# 612_jetracer_328_214.net
KiCad netlist of a schematic drawn in EAGLE
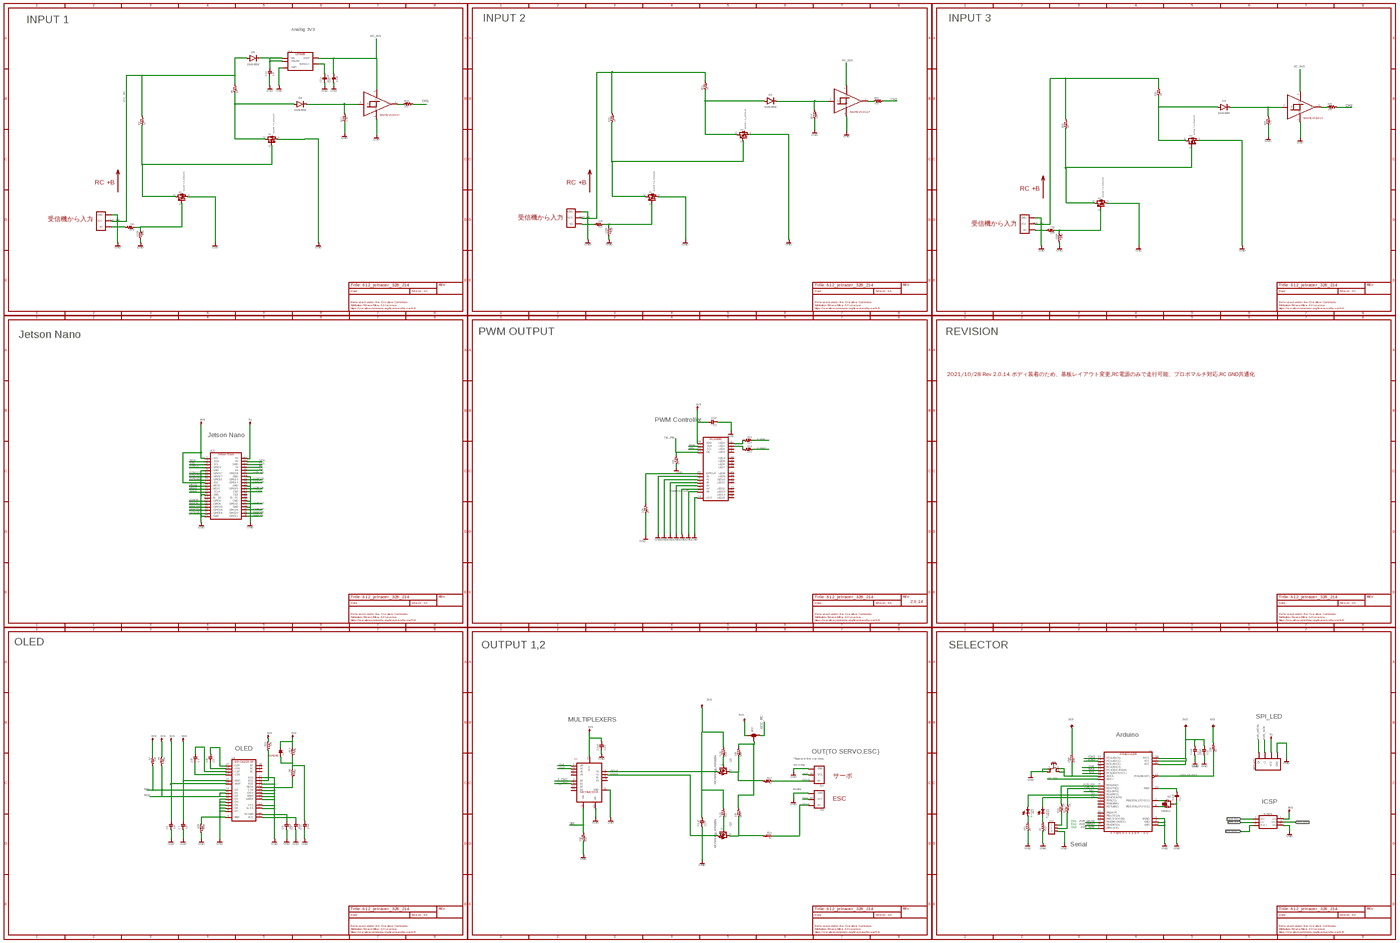
[diagram p0: schematic, sheet 1, overview]
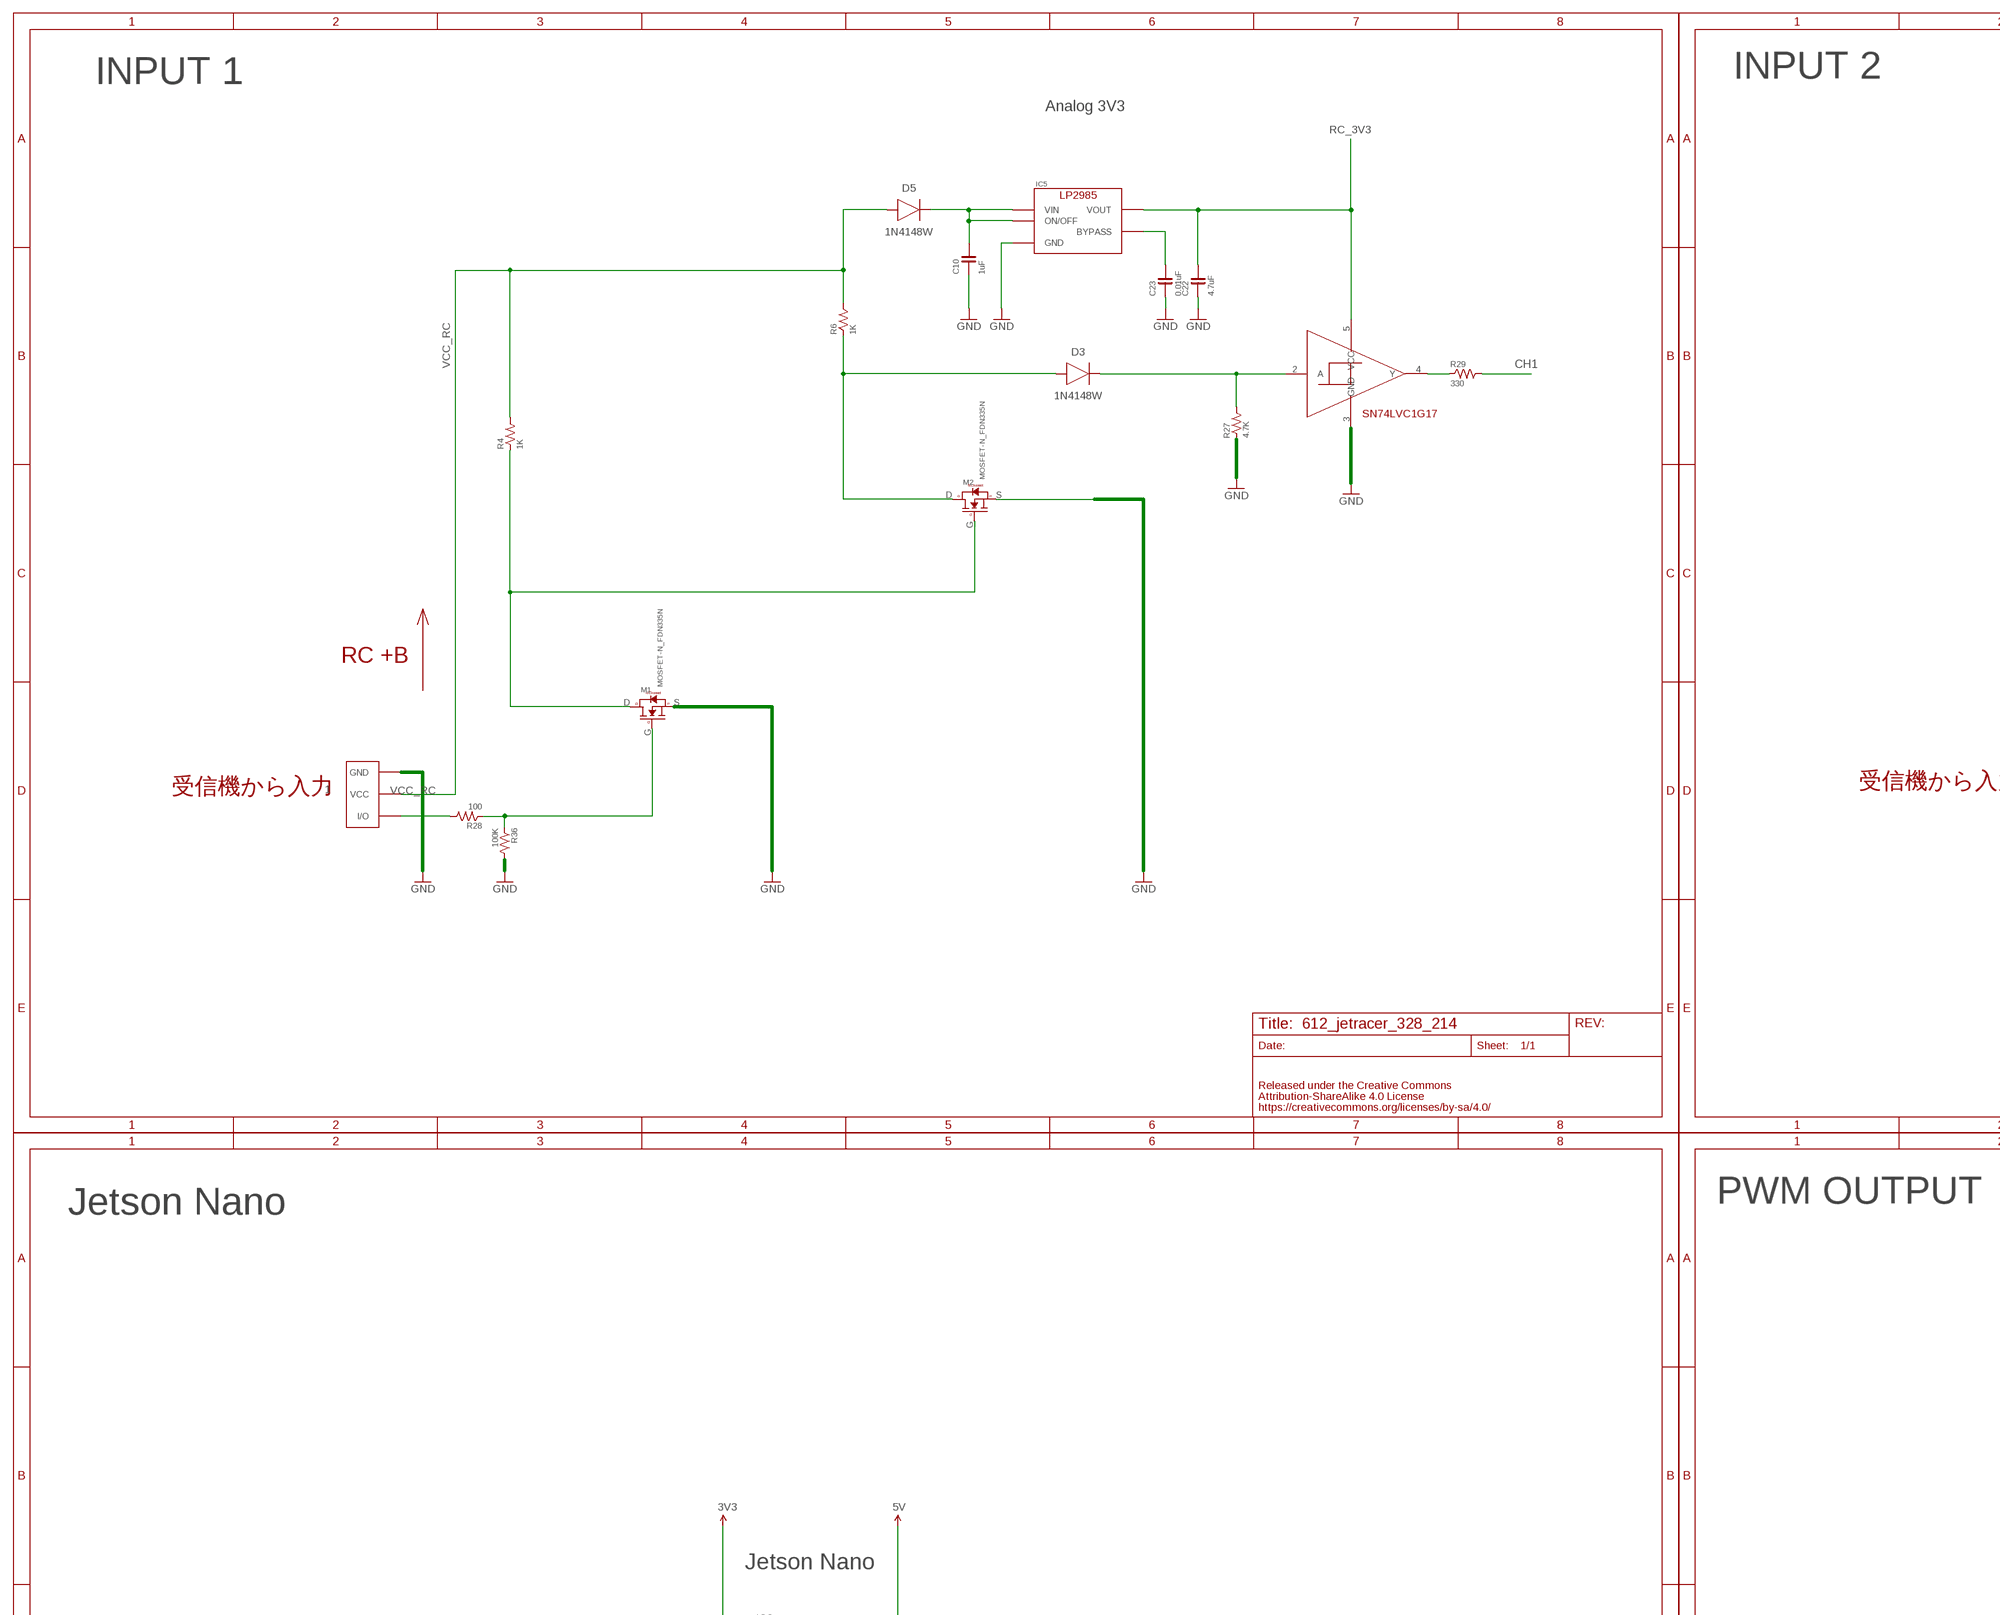
[diagram p1: schematic, sheet 1, part 1 of 6]
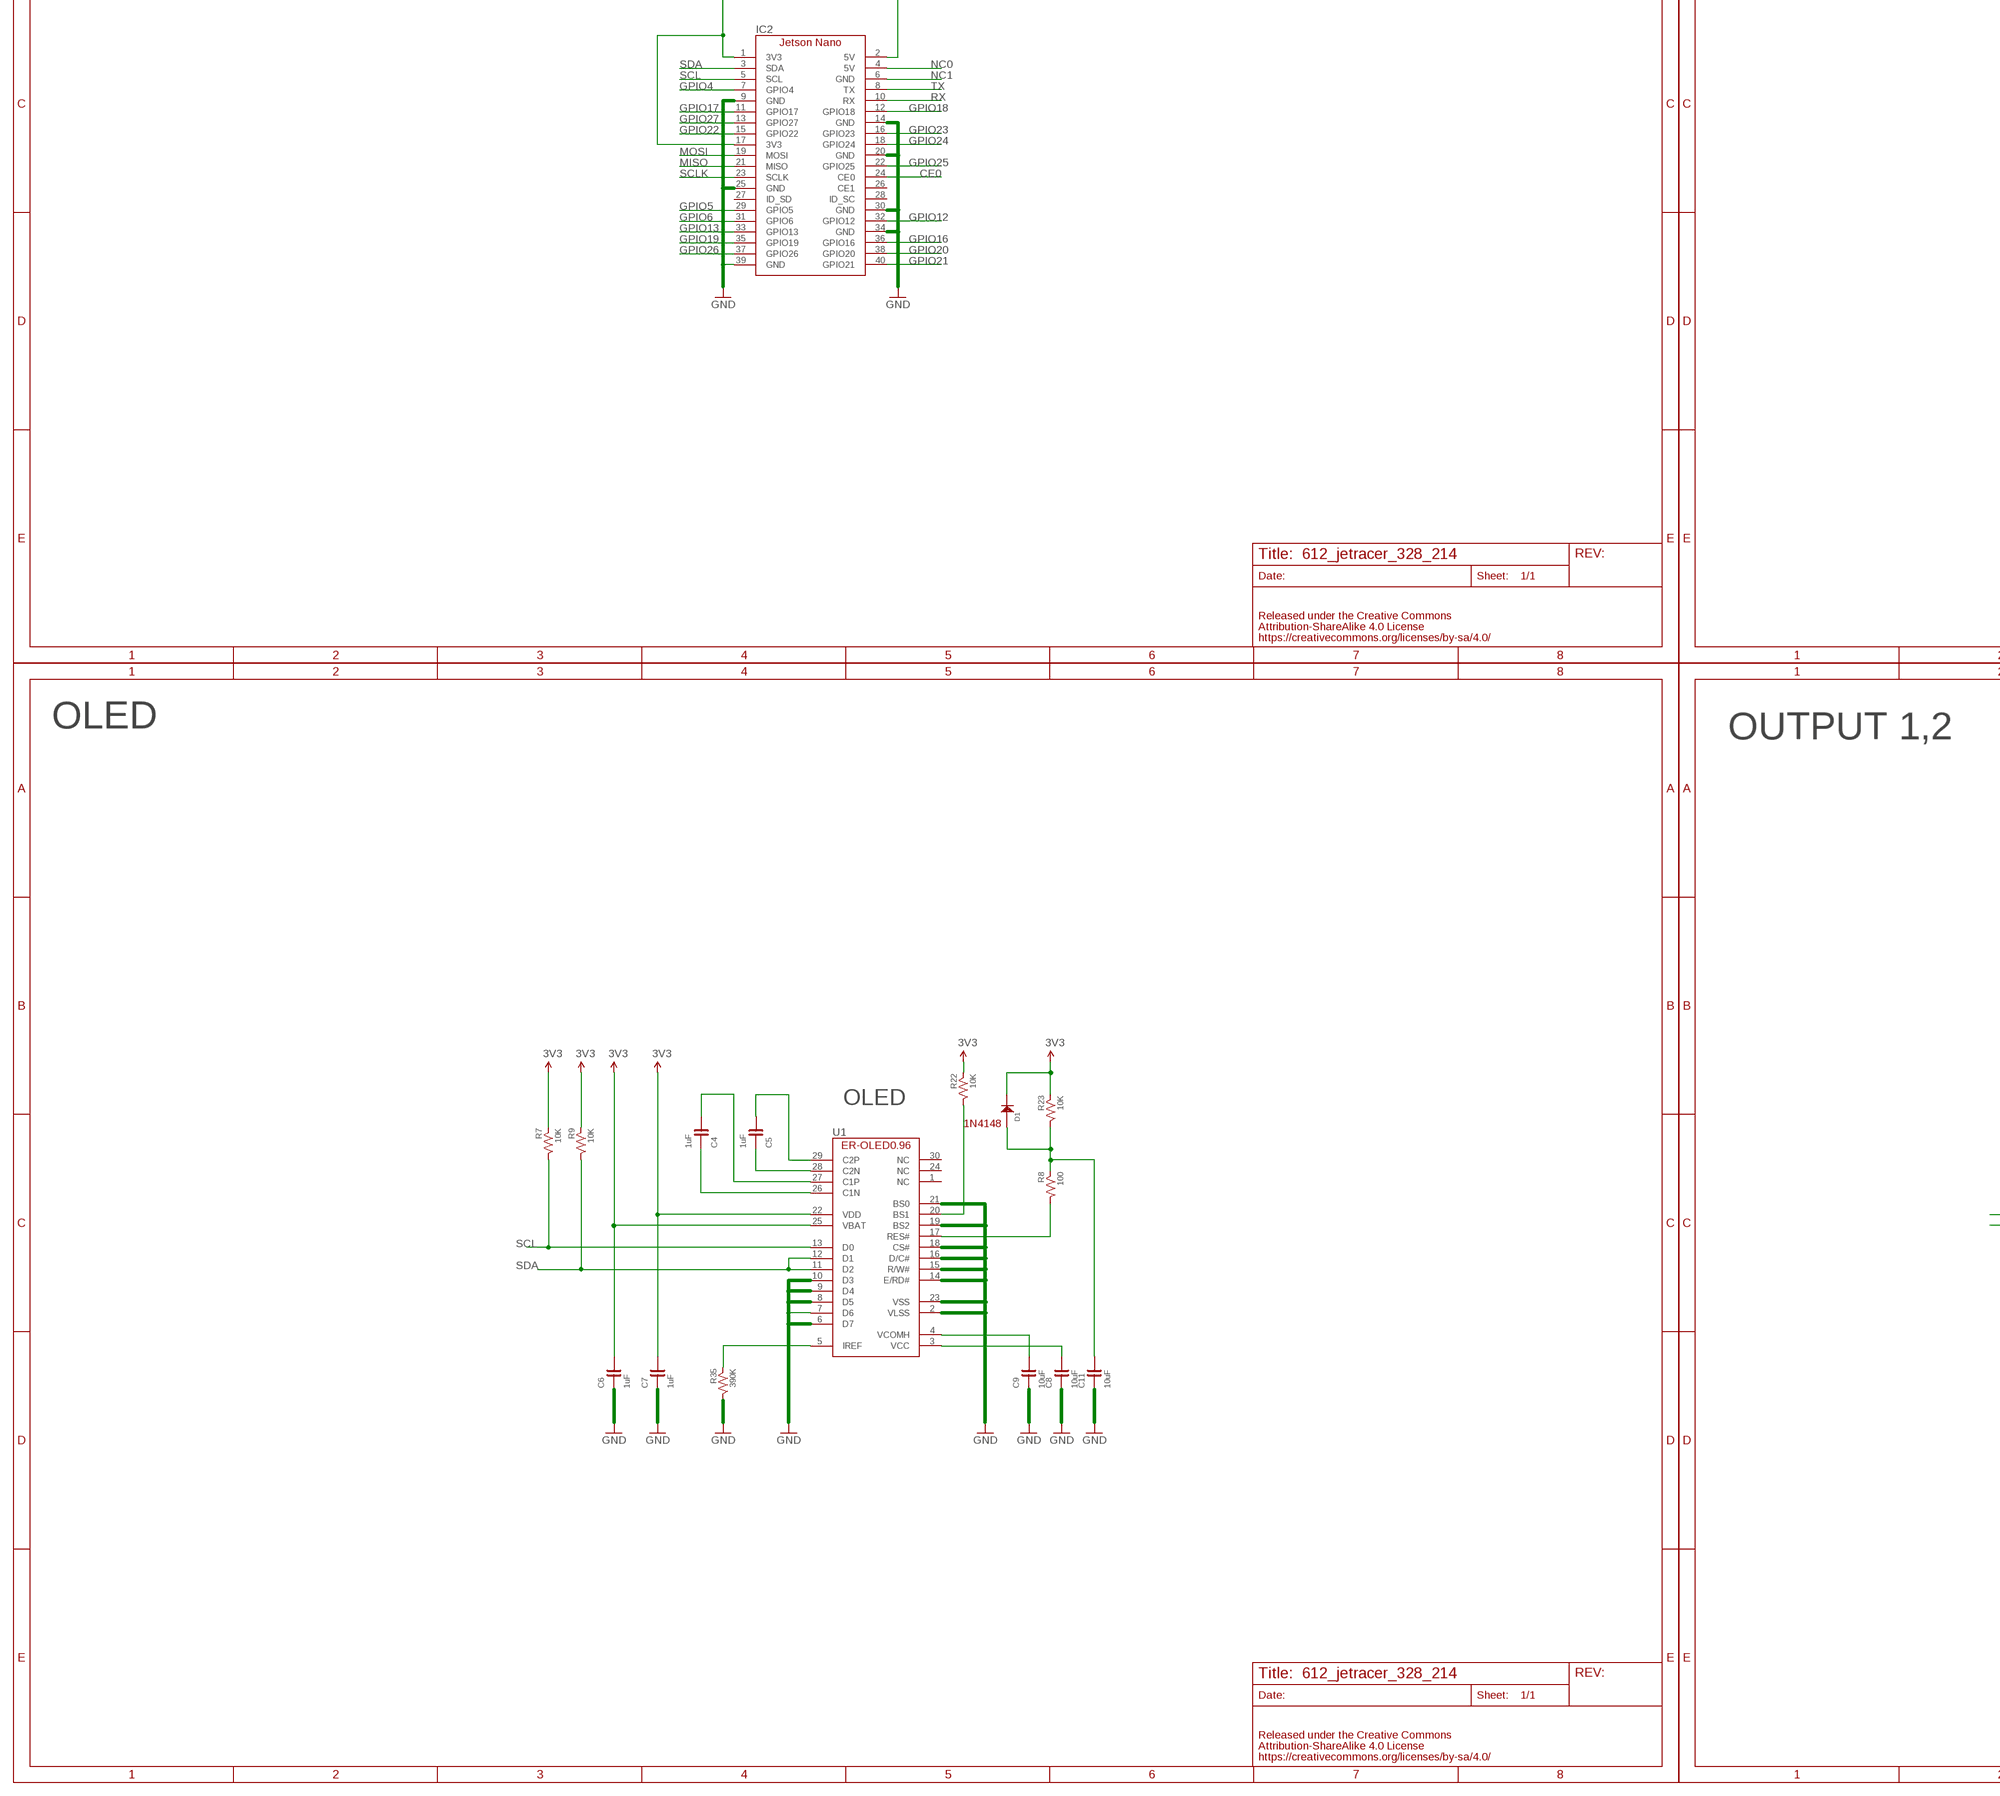
[diagram p2: schematic, sheet 1, part 2 of 6]
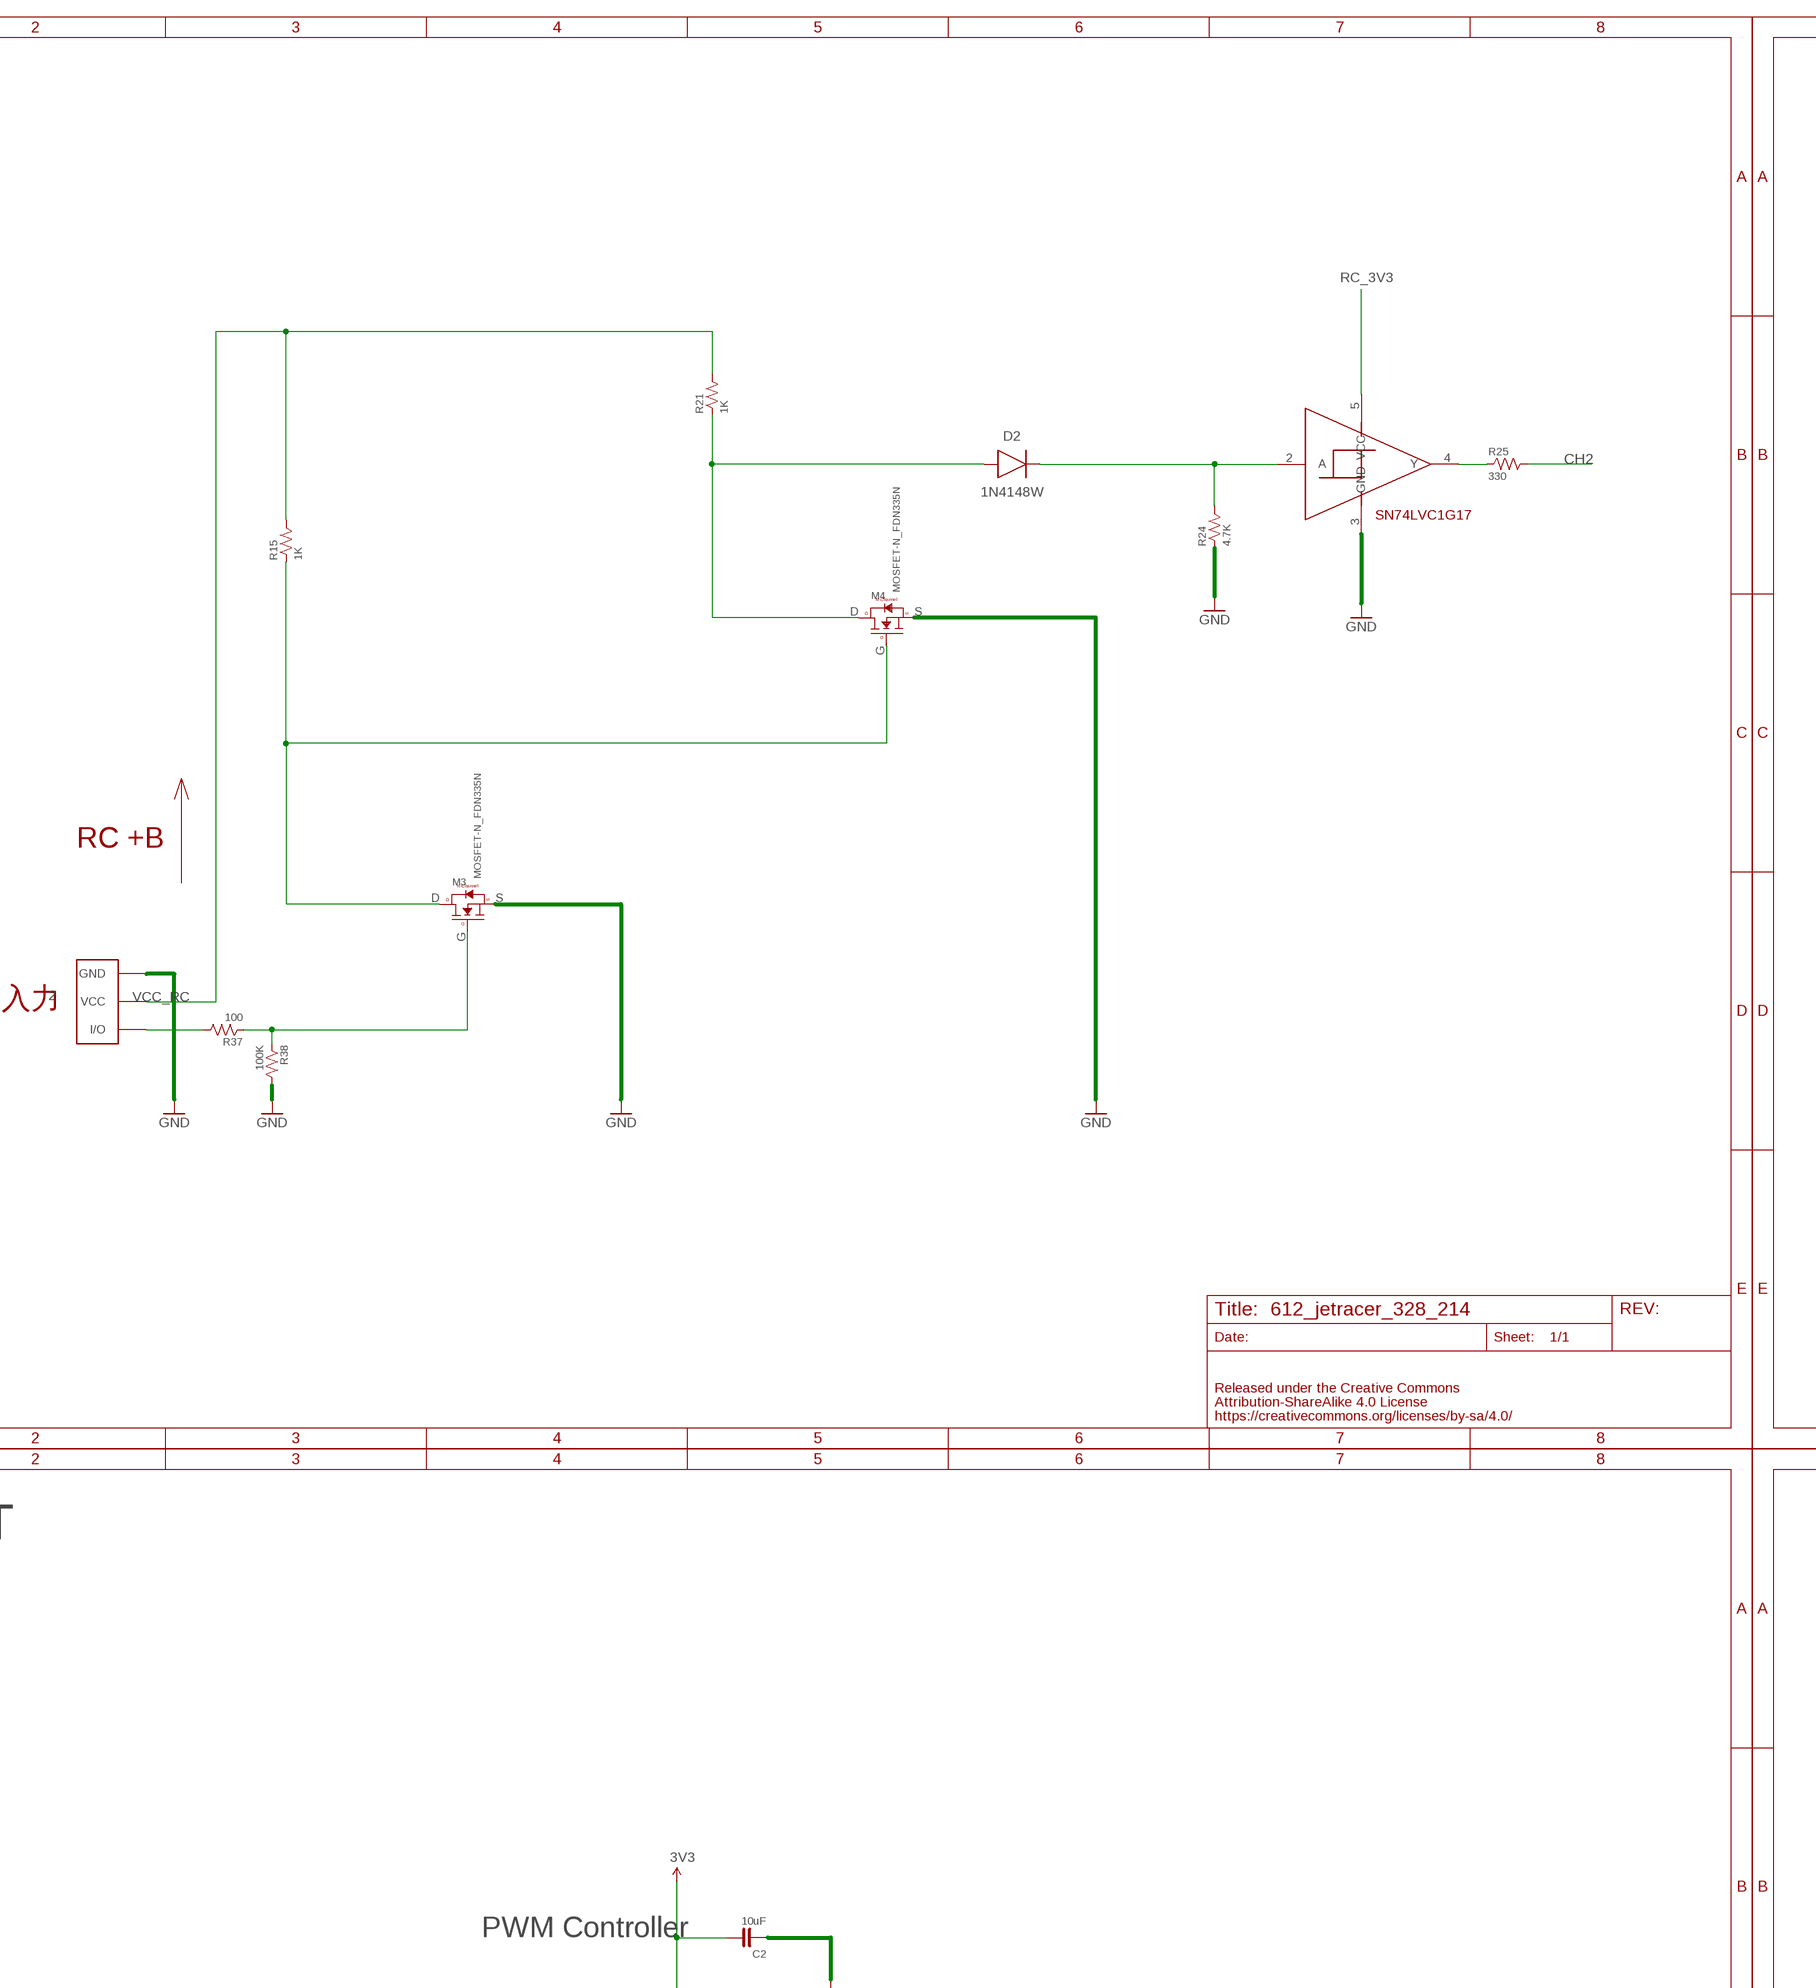
[diagram p3: schematic, sheet 1, part 3 of 6]
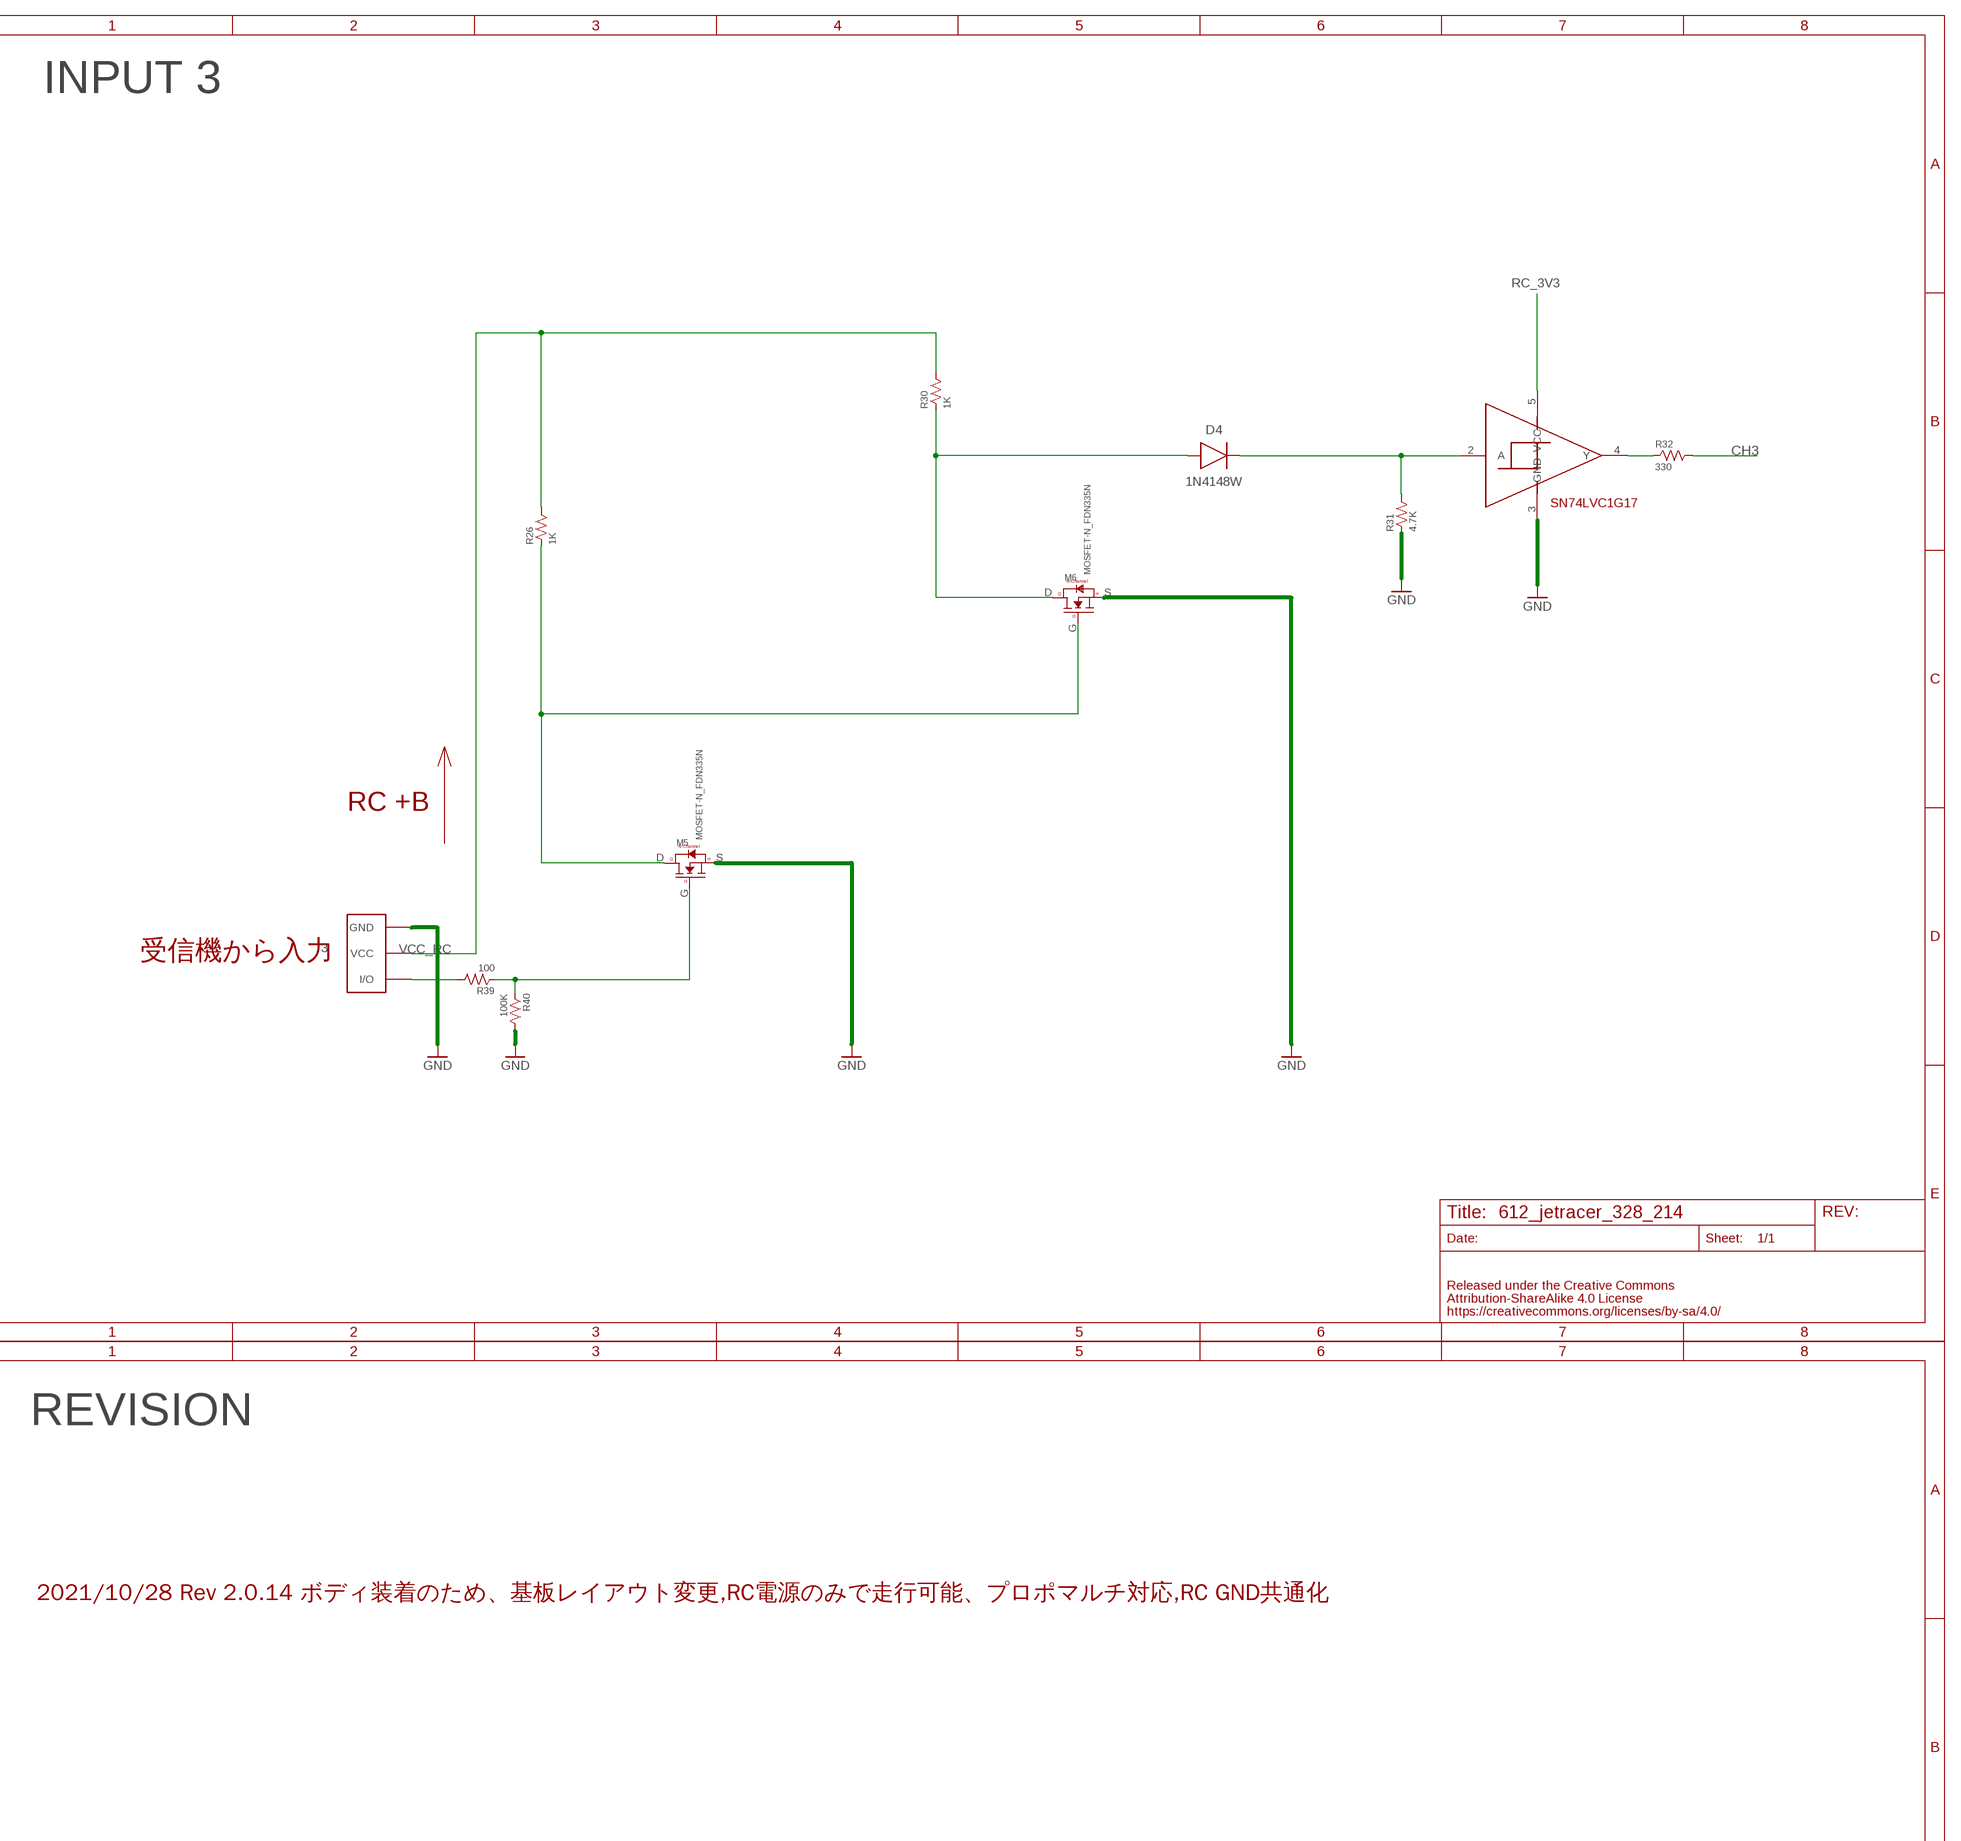
[diagram p4: schematic, sheet 1, part 4 of 6]
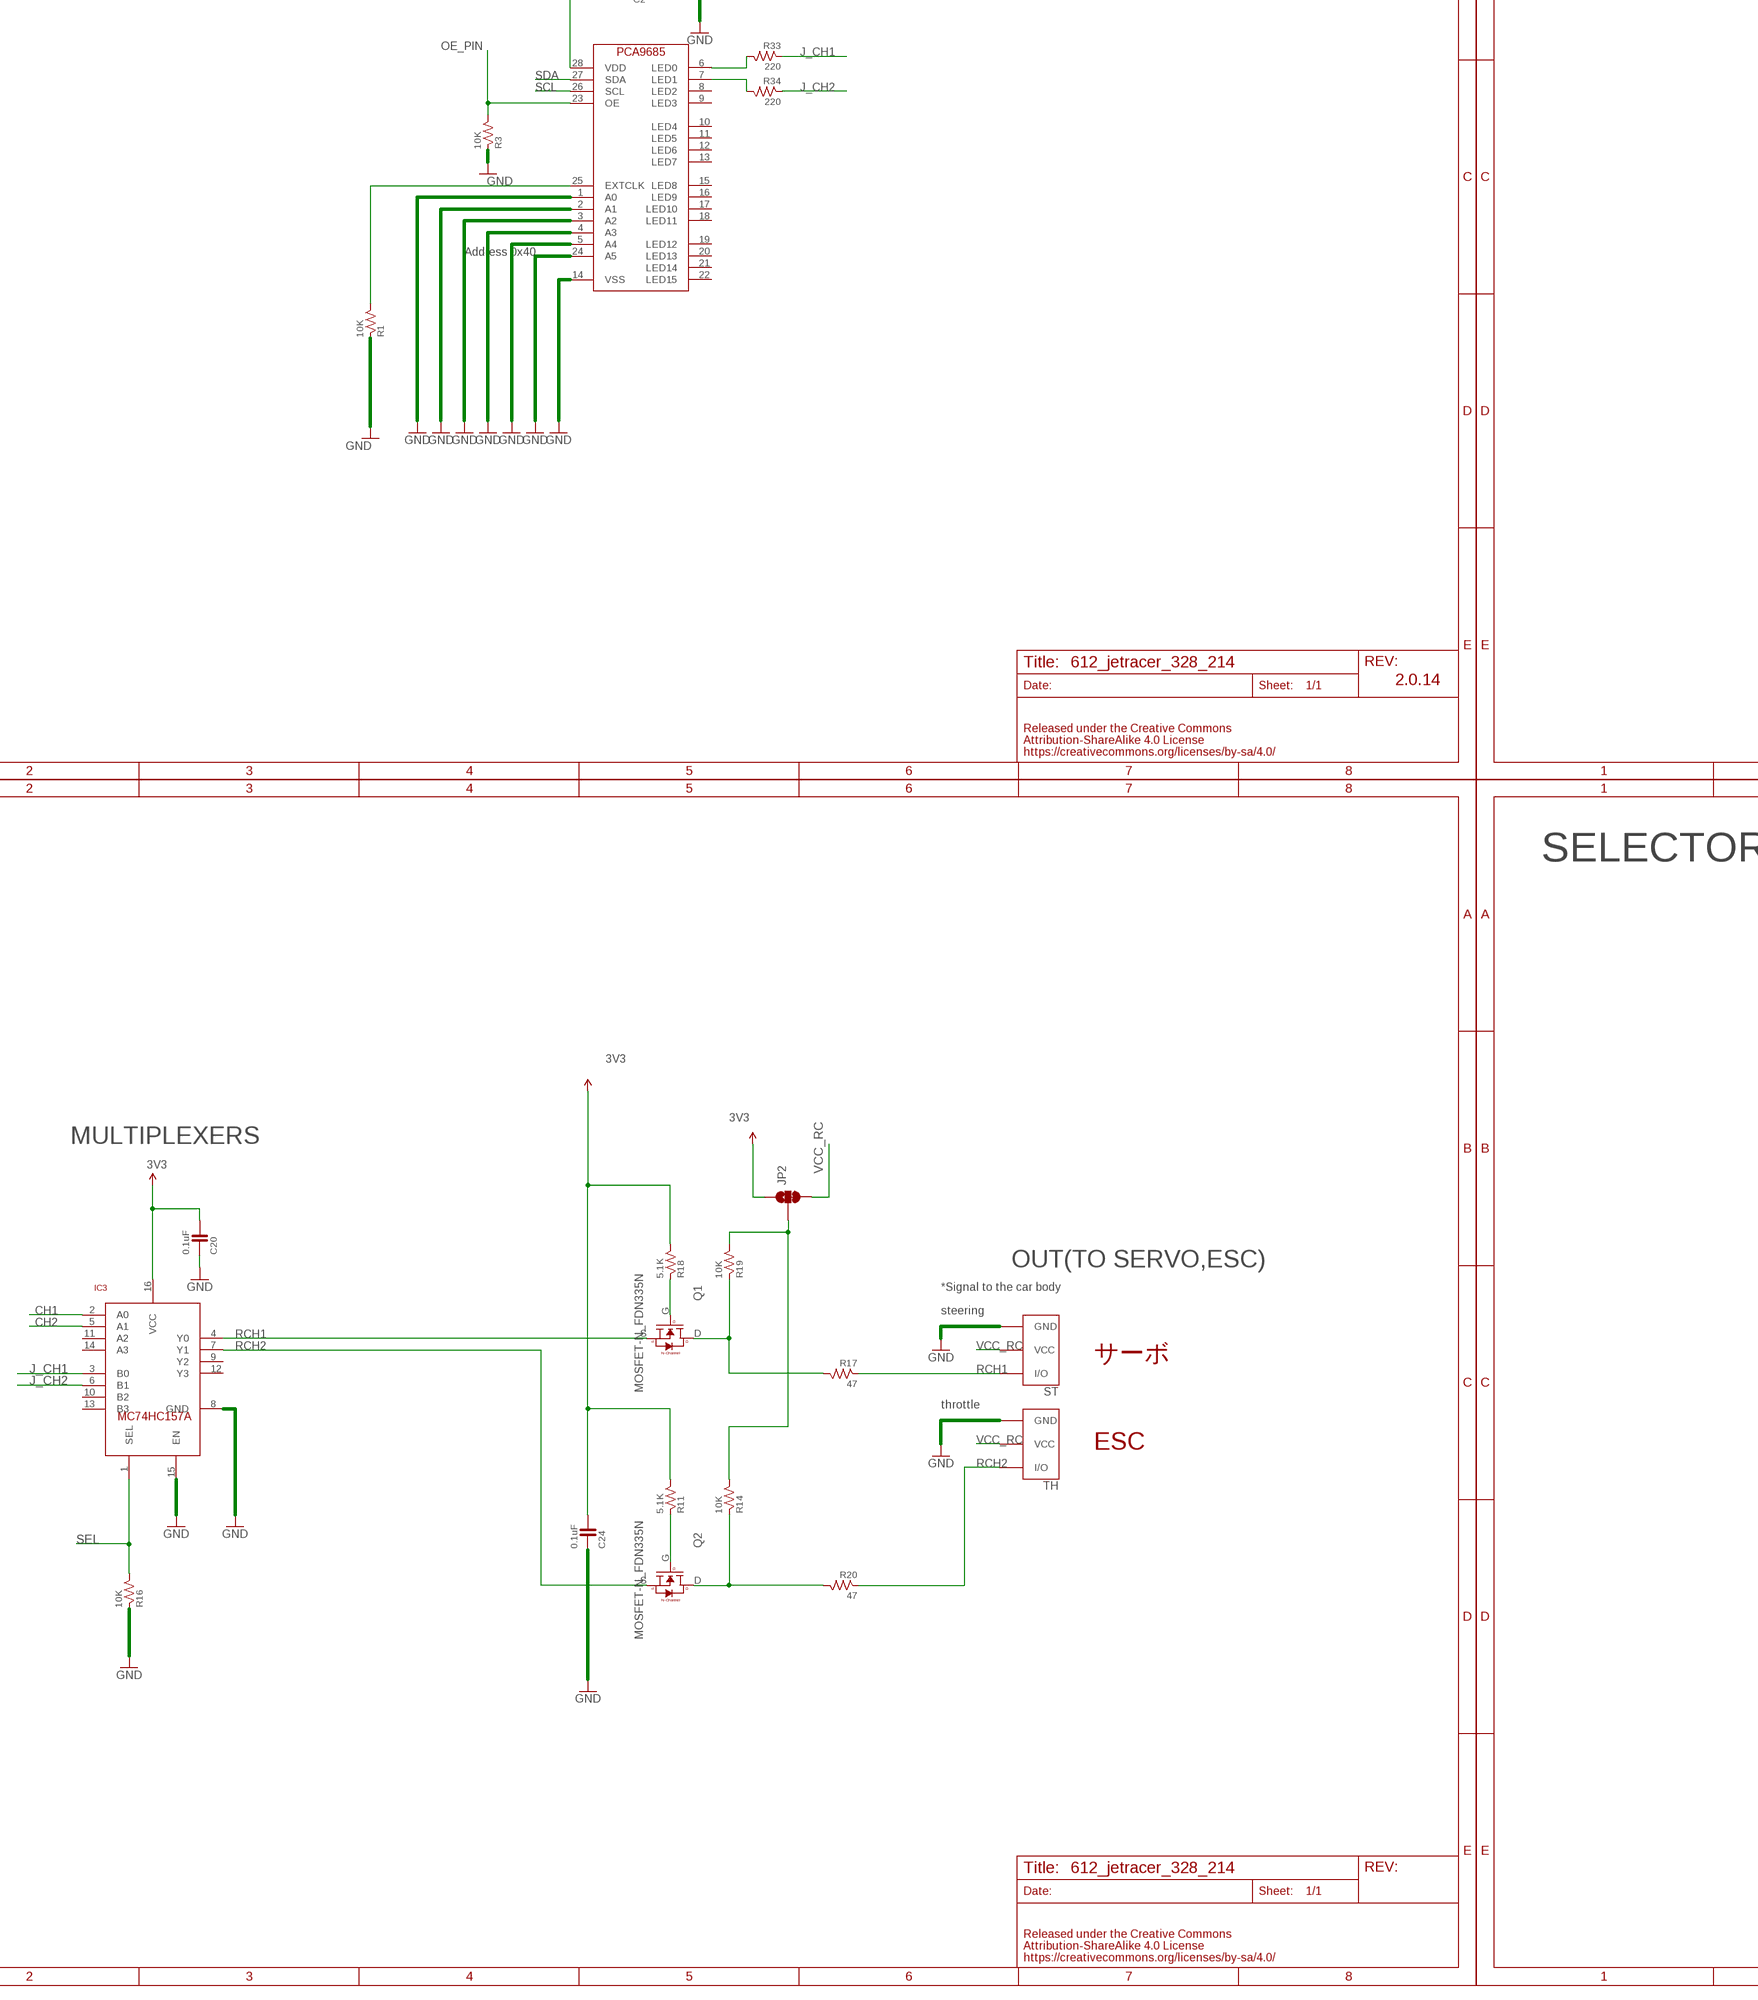
[diagram p5: schematic, sheet 1, part 5 of 6]
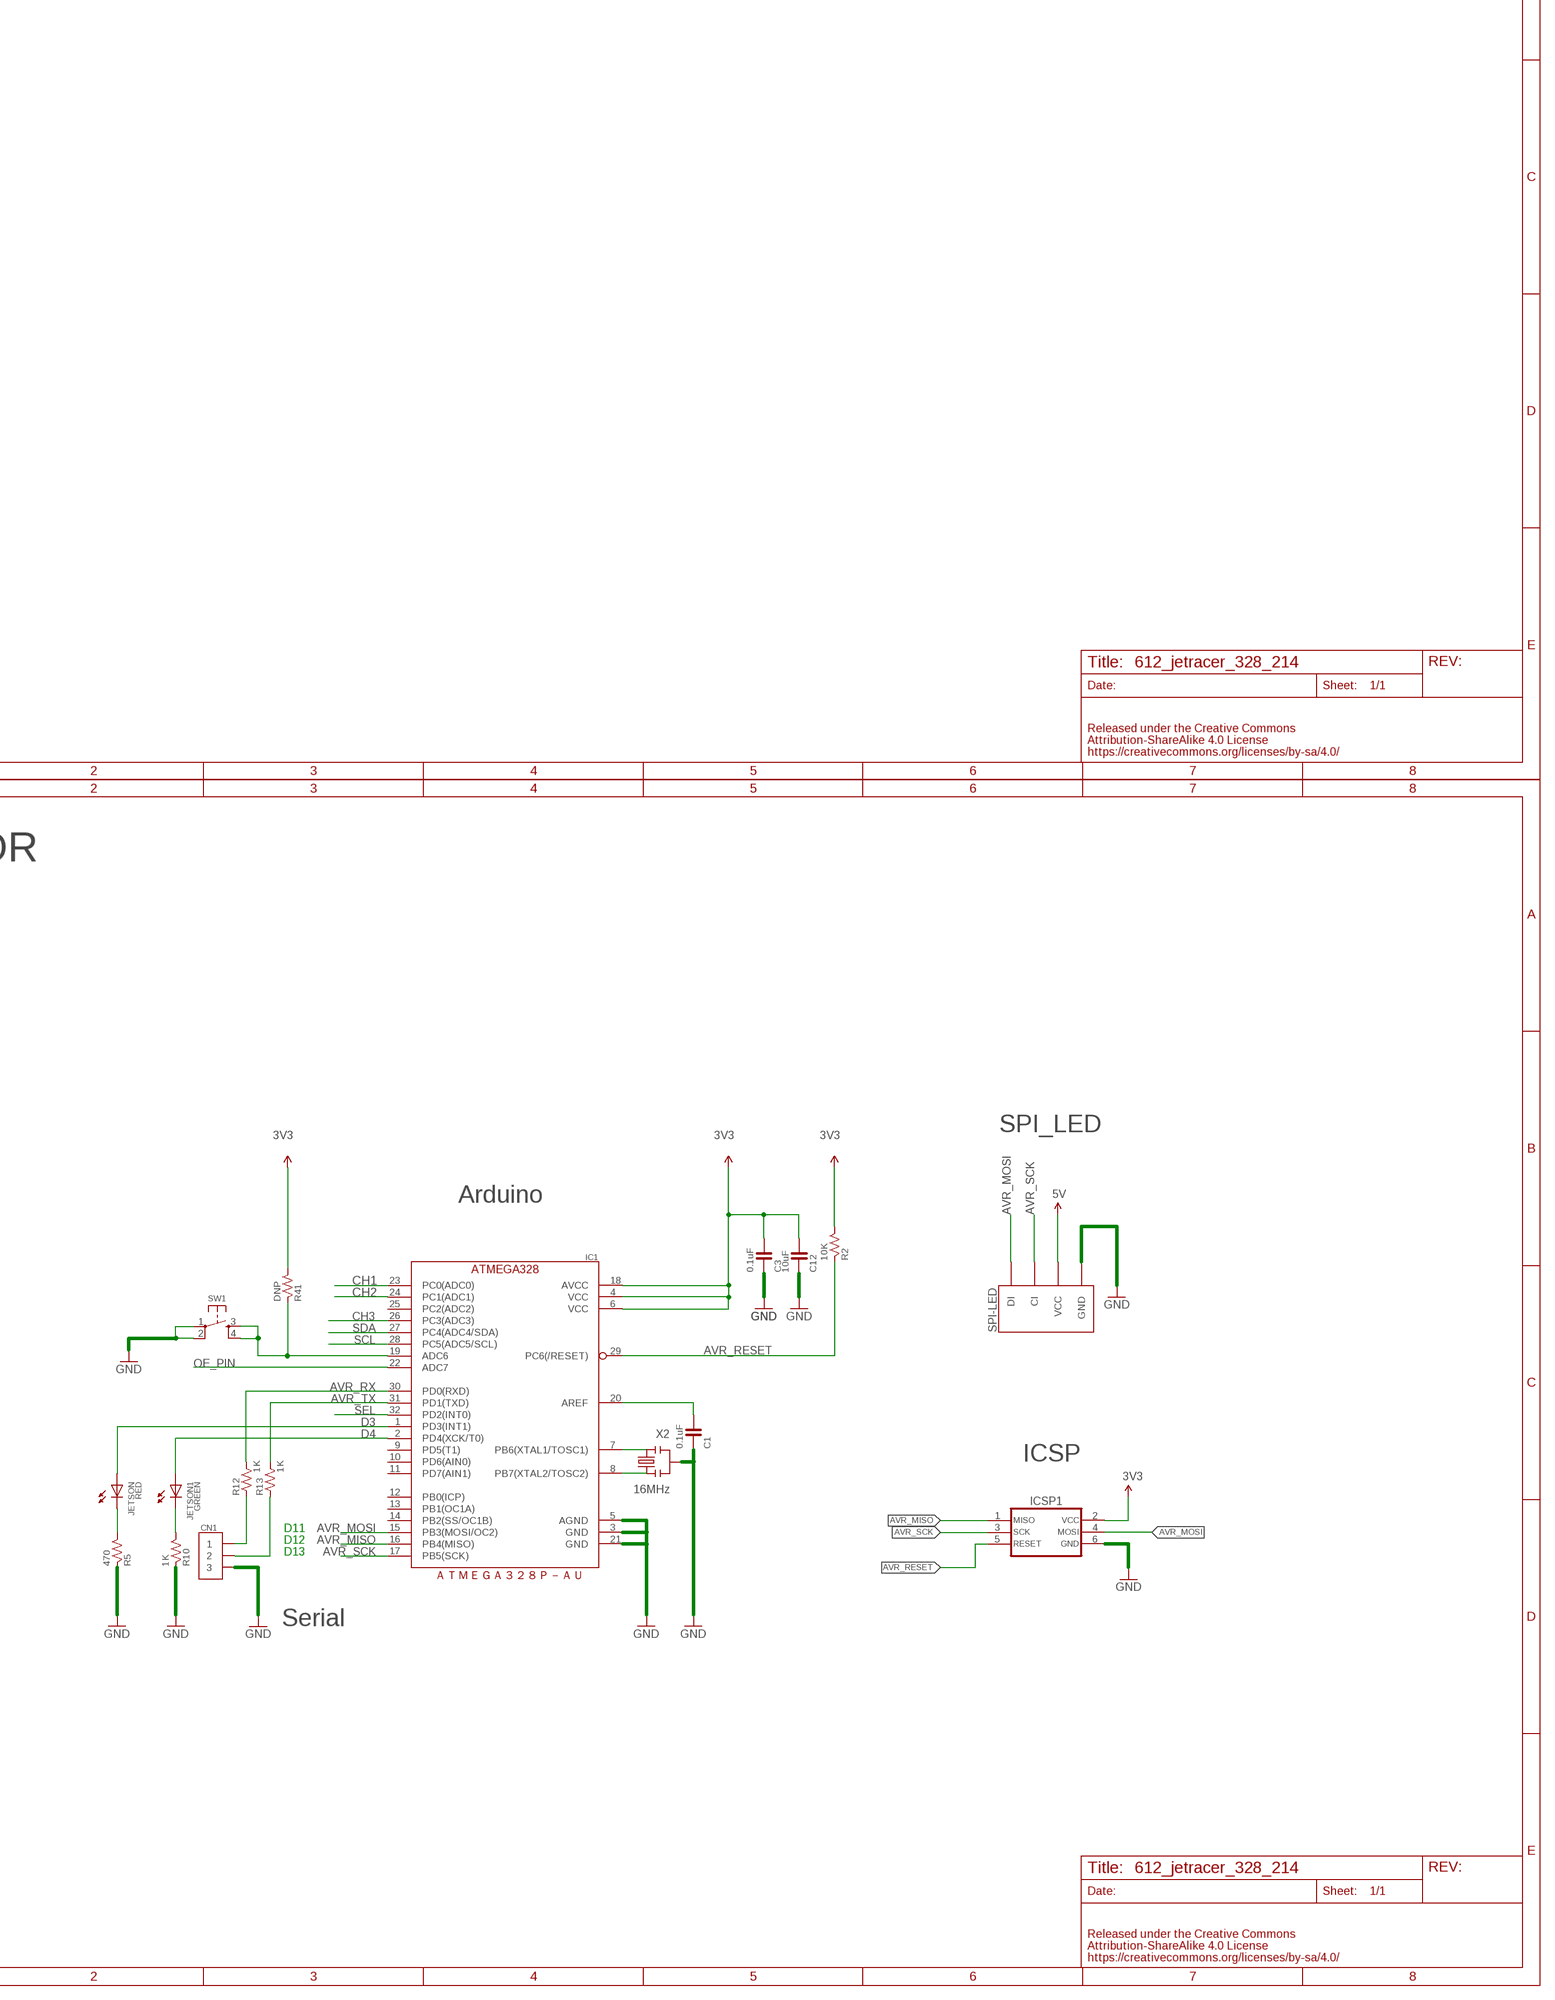
[diagram p6: schematic, sheet 1, part 6 of 6]

(export (version "E")
  (design (tool "Eeschema 10.0.6"))
  (components
    (comp (ref "1")
      (value "FABO_BRICK_3PIN-HEADER")
      (footprint "eagle-import:FABO_BRICK_3PIN_HEADER")
      (libsource (lib "eagle-import") (part "FABO_BRICK_3PIN-HEADER"))
    )
    (comp (ref "2")
      (value "FABO_BRICK_3PIN-HEADER")
      (footprint "eagle-import:FABO_BRICK_3PIN_HEADER")
      (libsource (lib "eagle-import") (part "FABO_BRICK_3PIN-HEADER"))
    )
    (comp (ref "3")
      (value "FABO_BRICK_3PIN-HEADER")
      (footprint "eagle-import:FABO_BRICK_3PIN_HEADER")
      (libsource (lib "eagle-import") (part "FABO_BRICK_3PIN-HEADER"))
    )
    (comp (ref "C1")
      (value "0.1uF")
      (footprint "eagle-import:0603")
      (libsource (lib "eagle-import") (part "CAPACITOR-0603"))
    )
    (comp (ref "C2")
      (value "10uF")
      (footprint "eagle-import:0603")
      (libsource (lib "eagle-import") (part "CAPACITOR-0603"))
    )
    (comp (ref "C3")
      (value "0.1uF")
      (footprint "eagle-import:0603")
      (libsource (lib "eagle-import") (part "CAPACITOR-0603"))
    )
    (comp (ref "C4")
      (value "1uF")
      (footprint "eagle-import:0603")
      (libsource (lib "eagle-import") (part "CAPACITOR-0603"))
    )
    (comp (ref "C5")
      (value "1uF")
      (footprint "eagle-import:0603")
      (libsource (lib "eagle-import") (part "CAPACITOR-0603"))
    )
    (comp (ref "C6")
      (value "1uF")
      (footprint "eagle-import:0603")
      (libsource (lib "eagle-import") (part "CAPACITOR-0603"))
    )
    (comp (ref "C7")
      (value "1uF")
      (footprint "eagle-import:0603")
      (libsource (lib "eagle-import") (part "CAPACITOR-0603"))
    )
    (comp (ref "C8")
      (value "10uF")
      (footprint "eagle-import:0603")
      (libsource (lib "eagle-import") (part "CAPACITOR-0603"))
    )
    (comp (ref "C9")
      (value "10uF")
      (footprint "eagle-import:0603")
      (libsource (lib "eagle-import") (part "CAPACITOR-0603"))
    )
    (comp (ref "C10")
      (value "1uF")
      (footprint "eagle-import:0603")
      (libsource (lib "eagle-import") (part "CAPACITOR-0603"))
    )
    (comp (ref "C11")
      (value "10uF")
      (footprint "eagle-import:0603")
      (libsource (lib "eagle-import") (part "CAPACITOR-0603"))
    )
    (comp (ref "C12")
      (value "10uF")
      (footprint "eagle-import:0603")
      (libsource (lib "eagle-import") (part "CAPACITOR-0603"))
    )
    (comp (ref "C20")
      (value "0.1uF")
      (footprint "eagle-import:0603")
      (libsource (lib "eagle-import") (part "CAPACITOR-0603"))
    )
    (comp (ref "C22")
      (value "4.7uF")
      (footprint "eagle-import:0603")
      (libsource (lib "eagle-import") (part "CAPACITOR-0603"))
    )
    (comp (ref "C23")
      (value "0.01uF")
      (footprint "eagle-import:0603")
      (libsource (lib "eagle-import") (part "CAPACITOR-0603"))
    )
    (comp (ref "C24")
      (value "0.1uF")
      (footprint "eagle-import:0603")
      (fields (field (name "SPICEPREFIX") "C"))
      (libsource (lib "eagle-import") (part "CAPACITOR-0603"))
    )
    (comp (ref "CN1")
      (value "PIN_1X3")
      (footprint "eagle-import:PIN_1X3")
      (libsource (lib "eagle-import") (part "PIN_1X3"))
    )
    (comp (ref "D1")
      (value "1N4148")
      (footprint "eagle-import:1N4148W")
      (libsource (lib "eagle-import") (part "1N4148"))
    )
    (comp (ref "D2")
      (value "1N4148W")
      (footprint "eagle-import:SOD3715X135")
      (fields (field (name "MANUFACTURER") "Diodes Incorporated"))
      (libsource (lib "eagle-import") (part "DIODE__SOD123G1N4148W-7-F"))
    )
    (comp (ref "D3")
      (value "1N4148W")
      (footprint "eagle-import:SOD3715X135")
      (fields (field (name "MANUFACTURER") "Diodes Incorporated"))
      (libsource (lib "eagle-import") (part "DIODE__SOD123G1N4148W-7-F"))
    )
    (comp (ref "D4")
      (value "1N4148W")
      (footprint "eagle-import:SOD3715X135")
      (fields (field (name "MANUFACTURER") "Diodes Incorporated"))
      (libsource (lib "eagle-import") (part "DIODE__SOD123G1N4148W-7-F"))
    )
    (comp (ref "D5")
      (value "1N4148W")
      (footprint "eagle-import:SOD3715X135")
      (fields (field (name "MANUFACTURER") "Diodes Incorporated"))
      (libsource (lib "eagle-import") (part "DIODE__SOD123G1N4148W-7-F"))
    )
    (comp (ref "IC1")
      (value "ATMEGA328P-AU")
      (footprint "eagle-import:TQFP-32")
      (libsource (lib "eagle-import") (part "ATMEGA328P-AU"))
    )
    (comp (ref "IC2")
      (value "JETSON_NANO_NOBORDER")
      (footprint "eagle-import:JETSON_NANO_NOBOARDER")
      (libsource (lib "eagle-import") (part "JETSON_NANO_NOBORDER"))
    )
    (comp (ref "IC3")
      (value "MULTIPLEXERSMC74HC157A")
      (footprint "eagle-import:TSSOP-16")
      (libsource (lib "eagle-import") (part "MULTIPLEXERSMC74HC157A"))
    )
    (comp (ref "IC4")
      (value "PCA9685")
      (footprint "eagle-import:PCA9685")
      (libsource (lib "eagle-import") (part "PCA9685"))
    )
    (comp (ref "IC5")
      (value "LP2985-33DBV")
      (footprint "eagle-import:SOT-23-5")
      (libsource (lib "eagle-import") (part "LP2985-33DBV"))
    )
    (comp (ref "ICSP1")
      (value "ICSP_AVR-TC_NOHOLE")
      (footprint "eagle-import:TC2030")
      (libsource (lib "eagle-import") (part "ICSP_AVR-TC_NOHOLE"))
    )
    (comp (ref "JETSON")
      (value "GREEN")
      (footprint "eagle-import:0603")
      (libsource (lib "eagle-import") (part "LED-0603"))
    )
    (comp (ref "JETSON1")
      (value "RED")
      (footprint "eagle-import:0603")
      (libsource (lib "eagle-import") (part "LED-0603"))
    )
    (comp (ref "JP2")
      (value "JUMPER-SMT_3_1-NC_TRACE_SILK")
      (footprint "eagle-import:SMT-JUMPER_3_1-NC_TRACE_SILK")
      (libsource (lib "eagle-import") (part "JUMPER-SMT_3_1-NC_TRACE_SILK"))
    )
    (comp (ref "M1")
      (value "MOSFET-N_FDN335N")
      (footprint "eagle-import:SUPERSOT-3")
      (libsource (lib "eagle-import") (part "MOSFET-N_FDN335N"))
    )
    (comp (ref "M2")
      (value "MOSFET-N_FDN335N")
      (footprint "eagle-import:SUPERSOT-3")
      (libsource (lib "eagle-import") (part "MOSFET-N_FDN335N"))
    )
    (comp (ref "M3")
      (value "MOSFET-N_FDN335N")
      (footprint "eagle-import:SUPERSOT-3")
      (libsource (lib "eagle-import") (part "MOSFET-N_FDN335N"))
    )
    (comp (ref "M4")
      (value "MOSFET-N_FDN335N")
      (footprint "eagle-import:SUPERSOT-3")
      (libsource (lib "eagle-import") (part "MOSFET-N_FDN335N"))
    )
    (comp (ref "M5")
      (value "MOSFET-N_FDN335N")
      (footprint "eagle-import:SUPERSOT-3")
      (libsource (lib "eagle-import") (part "MOSFET-N_FDN335N"))
    )
    (comp (ref "M6")
      (value "MOSFET-N_FDN335N")
      (footprint "eagle-import:SUPERSOT-3")
      (libsource (lib "eagle-import") (part "MOSFET-N_FDN335N"))
    )
    (comp (ref "Q1")
      (value "MOSFET-N_FDN335N")
      (footprint "eagle-import:SUPERSOT-3")
      (libsource (lib "eagle-import") (part "MOSFET-N_FDN335N"))
    )
    (comp (ref "Q2")
      (value "MOSFET-N_FDN335N")
      (footprint "eagle-import:SUPERSOT-3")
      (libsource (lib "eagle-import") (part "MOSFET-N_FDN335N"))
    )
    (comp (ref "R1")
      (value "10K")
      (footprint "eagle-import:0603")
      (libsource (lib "eagle-import") (part "RESISTOR-0603"))
    )
    (comp (ref "R2")
      (value "10K")
      (footprint "eagle-import:0603")
      (libsource (lib "eagle-import") (part "RESISTOR-0603"))
    )
    (comp (ref "R3")
      (value "10K")
      (footprint "eagle-import:0603")
      (libsource (lib "eagle-import") (part "RESISTOR-0603"))
    )
    (comp (ref "R4")
      (value "1K")
      (footprint "eagle-import:0603")
      (libsource (lib "eagle-import") (part "RESISTOR-0603"))
    )
    (comp (ref "R5")
      (value "470")
      (footprint "eagle-import:0603")
      (libsource (lib "eagle-import") (part "RESISTOR-0603"))
    )
    (comp (ref "R6")
      (value "1K")
      (footprint "eagle-import:0603")
      (libsource (lib "eagle-import") (part "RESISTOR-0603"))
    )
    (comp (ref "R7")
      (value "10K")
      (footprint "eagle-import:0603")
      (libsource (lib "eagle-import") (part "RESISTOR-0603"))
    )
    (comp (ref "R8")
      (value "100")
      (footprint "eagle-import:0603")
      (libsource (lib "eagle-import") (part "RESISTOR-0603"))
    )
    (comp (ref "R9")
      (value "10K")
      (footprint "eagle-import:0603")
      (libsource (lib "eagle-import") (part "RESISTOR-0603"))
    )
    (comp (ref "R10")
      (value "1K")
      (footprint "eagle-import:0603")
      (libsource (lib "eagle-import") (part "RESISTOR-0603"))
    )
    (comp (ref "R11")
      (value "5.1K")
      (footprint "eagle-import:0603")
      (libsource (lib "eagle-import") (part "RESISTOR-0603"))
    )
    (comp (ref "R12")
      (value "1K")
      (footprint "eagle-import:0603")
      (libsource (lib "eagle-import") (part "RESISTOR-0603"))
    )
    (comp (ref "R13")
      (value "1K")
      (footprint "eagle-import:0603")
      (libsource (lib "eagle-import") (part "RESISTOR-0603"))
    )
    (comp (ref "R14")
      (value "10K")
      (footprint "eagle-import:0603")
      (libsource (lib "eagle-import") (part "RESISTOR-0603"))
    )
    (comp (ref "R15")
      (value "1K")
      (footprint "eagle-import:0603")
      (libsource (lib "eagle-import") (part "RESISTOR-0603"))
    )
    (comp (ref "R16")
      (value "10K")
      (footprint "eagle-import:0603")
      (libsource (lib "eagle-import") (part "RESISTOR-0603"))
    )
    (comp (ref "R17")
      (value "47")
      (footprint "eagle-import:0603")
      (libsource (lib "eagle-import") (part "RESISTOR-0603"))
    )
    (comp (ref "R18")
      (value "5.1K")
      (footprint "eagle-import:0603")
      (libsource (lib "eagle-import") (part "RESISTOR-0603"))
    )
    (comp (ref "R19")
      (value "10K")
      (footprint "eagle-import:0603")
      (libsource (lib "eagle-import") (part "RESISTOR-0603"))
    )
    (comp (ref "R20")
      (value "47")
      (footprint "eagle-import:0603")
      (libsource (lib "eagle-import") (part "RESISTOR-0603"))
    )
    (comp (ref "R21")
      (value "1K")
      (footprint "eagle-import:0603")
      (libsource (lib "eagle-import") (part "RESISTOR-0603"))
    )
    (comp (ref "R22")
      (value "10K")
      (footprint "eagle-import:0603")
      (libsource (lib "eagle-import") (part "RESISTOR-0603"))
    )
    (comp (ref "R23")
      (value "10K")
      (footprint "eagle-import:0603")
      (libsource (lib "eagle-import") (part "RESISTOR-0603"))
    )
    (comp (ref "R24")
      (value "4.7K")
      (footprint "eagle-import:0603")
      (libsource (lib "eagle-import") (part "RESISTOR-0603"))
    )
    (comp (ref "R25")
      (value "330")
      (footprint "eagle-import:0603")
      (libsource (lib "eagle-import") (part "RESISTOR-0603"))
    )
    (comp (ref "R26")
      (value "1K")
      (footprint "eagle-import:0603")
      (libsource (lib "eagle-import") (part "RESISTOR-0603"))
    )
    (comp (ref "R27")
      (value "4.7K")
      (footprint "eagle-import:0603")
      (libsource (lib "eagle-import") (part "RESISTOR-0603"))
    )
    (comp (ref "R28")
      (value "100")
      (footprint "eagle-import:0603")
      (libsource (lib "eagle-import") (part "RESISTOR-0603"))
    )
    (comp (ref "R29")
      (value "330")
      (footprint "eagle-import:0603")
      (libsource (lib "eagle-import") (part "RESISTOR-0603"))
    )
    (comp (ref "R30")
      (value "1K")
      (footprint "eagle-import:0603")
      (libsource (lib "eagle-import") (part "RESISTOR-0603"))
    )
    (comp (ref "R31")
      (value "4.7K")
      (footprint "eagle-import:0603")
      (libsource (lib "eagle-import") (part "RESISTOR-0603"))
    )
    (comp (ref "R32")
      (value "330")
      (footprint "eagle-import:0603")
      (libsource (lib "eagle-import") (part "RESISTOR-0603"))
    )
    (comp (ref "R33")
      (value "220")
      (footprint "eagle-import:0603")
      (libsource (lib "eagle-import") (part "RESISTOR-0603"))
    )
    (comp (ref "R34")
      (value "220")
      (footprint "eagle-import:0603")
      (libsource (lib "eagle-import") (part "RESISTOR-0603"))
    )
    (comp (ref "R35")
      (value "390K")
      (footprint "eagle-import:0603")
      (libsource (lib "eagle-import") (part "RESISTOR-0603"))
    )
    (comp (ref "R36")
      (value "100K")
      (footprint "eagle-import:0603")
      (libsource (lib "eagle-import") (part "RESISTOR-0603"))
    )
    (comp (ref "R37")
      (value "100")
      (footprint "eagle-import:0603")
      (libsource (lib "eagle-import") (part "RESISTOR-0603"))
    )
    (comp (ref "R38")
      (value "100K")
      (footprint "eagle-import:0603")
      (libsource (lib "eagle-import") (part "RESISTOR-0603"))
    )
    (comp (ref "R39")
      (value "100")
      (footprint "eagle-import:0603")
      (libsource (lib "eagle-import") (part "RESISTOR-0603"))
    )
    (comp (ref "R40")
      (value "100K")
      (footprint "eagle-import:0603")
      (libsource (lib "eagle-import") (part "RESISTOR-0603"))
    )
    (comp (ref "R41")
      (value "DNP")
      (footprint "eagle-import:0603")
      (libsource (lib "eagle-import") (part "RESISTOR-0603"))
    )
    (comp (ref "SPI-LED")
      (value "FABO-SPI-LED-B04B")
      (footprint "eagle-import:SPI-B04B-PASK-1")
      (libsource (lib "eagle-import") (part "FABO-SPI-LED-B04B"))
    )
    (comp (ref "ST")
      (value "FABO_BRICK_3PIN-HEADER")
      (footprint "eagle-import:FABO_BRICK_3PIN_HEADER")
      (libsource (lib "eagle-import") (part "FABO_BRICK_3PIN-HEADER"))
    )
    (comp (ref "SW1")
      (value "TACT-SWITCH-SMD_KMR2")
      (footprint "eagle-import:KMR2")
      (libsource (lib "eagle-import") (part "TACT-SWITCH-SMD_KMR2"))
    )
    (comp (ref "TH")
      (value "FABO_BRICK_3PIN-HEADER")
      (footprint "eagle-import:FABO_BRICK_3PIN_HEADER")
      (libsource (lib "eagle-import") (part "FABO_BRICK_3PIN-HEADER"))
    )
    (comp (ref "U$14")
      (value "SN74LVC1G17")
      (footprint "eagle-import:SOT-23")
      (libsource (lib "eagle-import") (part "SN74LVC1G17"))
    )
    (comp (ref "U$20")
      (value "SN74LVC1G17")
      (footprint "eagle-import:SOT-23")
      (libsource (lib "eagle-import") (part "SN74LVC1G17"))
    )
    (comp (ref "U$23")
      (value "SN74LVC1G17")
      (footprint "eagle-import:SOT-23")
      (libsource (lib "eagle-import") (part "SN74LVC1G17"))
    )
    (comp (ref "U1")
      (value "ER-OLED0.96-1ER-CON30HT-1")
      (footprint "eagle-import:ER-CON30HT-1")
      (libsource (lib "eagle-import") (part "ER-OLED0.96-1ER-CON30HT-1"))
    )
    (comp (ref "X2")
      (value "16MHz")
      (footprint "eagle-import:CSTNE_V_C")
      (libsource (lib "eagle-import") (part "RESONATOR"))
    )
  )
  (nets
    (net (code "1") (name "/AVR_RX") (class "Default")
      (node (ref "IC1") (pin "30") (pinfunction "PD0(RXD)_30") (pintype "bidirectional"))
      (node (ref "R12") (pin "2") (pinfunction "2_2") (pintype "bidirectional"))
    )
    (net (code "2") (name "/AVR_TX") (class "Default")
      (node (ref "IC1") (pin "31") (pinfunction "PD1(TXD)_31") (pintype "bidirectional"))
      (node (ref "R13") (pin "2") (pinfunction "2_2") (pintype "bidirectional"))
    )
    (net (code "3") (name "/CE0") (class "Default")
      (node (ref "IC2") (pin "24") (pinfunction "CE0_24") (pintype "bidirectional"))
    )
    (net (code "4") (name "/CH1") (class "Default")
      (node (ref "IC1") (pin "23") (pinfunction "PC0(ADC0)_23") (pintype "bidirectional"))
      (node (ref "IC3") (pin "2") (pinfunction "A0_2") (pintype "bidirectional"))
      (node (ref "R29") (pin "2") (pinfunction "2_2") (pintype "bidirectional"))
    )
    (net (code "5") (name "/CH2") (class "Default")
      (node (ref "IC1") (pin "24") (pinfunction "PC1(ADC1)_24") (pintype "bidirectional"))
      (node (ref "IC3") (pin "5") (pinfunction "A1_5") (pintype "bidirectional"))
      (node (ref "R25") (pin "2") (pinfunction "2_2") (pintype "bidirectional"))
    )
    (net (code "6") (name "/CH3") (class "Default")
      (node (ref "IC1") (pin "26") (pinfunction "PC3(ADC3)_26") (pintype "bidirectional"))
      (node (ref "R32") (pin "2") (pinfunction "2_2") (pintype "bidirectional"))
    )
    (net (code "7") (name "/D3") (class "Default")
      (node (ref "IC1") (pin "1") (pinfunction "PD3(INT1)_1") (pintype "bidirectional"))
      (node (ref "JETSON1") (pin "ANODE") (pinfunction "ANODE_ANODE") (pintype "passive"))
    )
    (net (code "8") (name "/D4") (class "Default")
      (node (ref "IC1") (pin "2") (pinfunction "PD4(XCK/T0)_2") (pintype "bidirectional"))
      (node (ref "JETSON") (pin "ANODE") (pinfunction "ANODE_ANODE") (pintype "passive"))
    )
    (net (code "9") (name "/GPIO4") (class "Default")
      (node (ref "IC2") (pin "7") (pinfunction "GPIO4_7") (pintype "bidirectional"))
    )
    (net (code "10") (name "/GPIO5") (class "Default")
      (node (ref "IC2") (pin "29") (pinfunction "GPIO5_29") (pintype "bidirectional"))
    )
    (net (code "11") (name "/GPIO6") (class "Default")
      (node (ref "IC2") (pin "31") (pinfunction "GPIO6_31") (pintype "bidirectional"))
    )
    (net (code "12") (name "/GPIO12") (class "Default")
      (node (ref "IC2") (pin "32") (pinfunction "GPIO12_32") (pintype "bidirectional"))
    )
    (net (code "13") (name "/GPIO13") (class "Default")
      (node (ref "IC2") (pin "33") (pinfunction "GPIO13_33") (pintype "bidirectional"))
    )
    (net (code "14") (name "/GPIO16") (class "Default")
      (node (ref "IC2") (pin "36") (pinfunction "GPIO16_36") (pintype "bidirectional"))
    )
    (net (code "15") (name "/GPIO17") (class "Default")
      (node (ref "IC2") (pin "11") (pinfunction "GPIO17_11") (pintype "bidirectional"))
    )
    (net (code "16") (name "/GPIO18") (class "Default")
      (node (ref "IC2") (pin "12") (pinfunction "GPIO18_12") (pintype "bidirectional"))
    )
    (net (code "17") (name "/GPIO19") (class "Default")
      (node (ref "IC2") (pin "35") (pinfunction "GPIO19_35") (pintype "bidirectional"))
    )
    (net (code "18") (name "/GPIO20") (class "Default")
      (node (ref "IC2") (pin "38") (pinfunction "GPIO20_38") (pintype "bidirectional"))
    )
    (net (code "19") (name "/GPIO21") (class "Default")
      (node (ref "IC2") (pin "40") (pinfunction "GPIO21_40") (pintype "bidirectional"))
    )
    (net (code "20") (name "/GPIO22") (class "Default")
      (node (ref "IC2") (pin "15") (pinfunction "GPIO22_15") (pintype "bidirectional"))
    )
    (net (code "21") (name "/GPIO23") (class "Default")
      (node (ref "IC2") (pin "16") (pinfunction "GPIO23_16") (pintype "bidirectional"))
    )
    (net (code "22") (name "/GPIO24") (class "Default")
      (node (ref "IC2") (pin "18") (pinfunction "GPIO24_18") (pintype "bidirectional"))
    )
    (net (code "23") (name "/GPIO25") (class "Default")
      (node (ref "IC2") (pin "22") (pinfunction "GPIO25_22") (pintype "bidirectional"))
    )
    (net (code "24") (name "/GPIO26") (class "Default")
      (node (ref "IC2") (pin "37") (pinfunction "GPIO26_37") (pintype "bidirectional"))
    )
    (net (code "25") (name "/GPIO27") (class "Default")
      (node (ref "IC2") (pin "13") (pinfunction "GPIO27_13") (pintype "bidirectional"))
    )
    (net (code "26") (name "/J_CH1") (class "Default")
      (node (ref "IC3") (pin "3") (pinfunction "B0_3") (pintype "bidirectional"))
      (node (ref "R33") (pin "1") (pinfunction "1_1") (pintype "bidirectional"))
    )
    (net (code "27") (name "/J_CH2") (class "Default")
      (node (ref "IC3") (pin "6") (pinfunction "B1_6") (pintype "bidirectional"))
      (node (ref "R34") (pin "1") (pinfunction "1_1") (pintype "bidirectional"))
    )
    (net (code "28") (name "/MISO") (class "Default")
      (node (ref "IC2") (pin "21") (pinfunction "MISO_21") (pintype "bidirectional"))
    )
    (net (code "29") (name "/MOSI") (class "Default")
      (node (ref "IC2") (pin "19") (pinfunction "MOSI_19") (pintype "bidirectional"))
    )
    (net (code "30") (name "/NC0") (class "Default")
      (node (ref "IC2") (pin "4") (pinfunction "5V_4") (pintype "bidirectional"))
    )
    (net (code "31") (name "/NC1") (class "Default")
      (node (ref "IC2") (pin "6") (pinfunction "GND_6") (pintype "bidirectional"))
    )
    (net (code "32") (name "/OE_PIN") (class "Default")
      (node (ref "IC1") (pin "22") (pinfunction "ADC7_22") (pintype "bidirectional"))
      (node (ref "IC4") (pin "23") (pinfunction "OE_23") (pintype "bidirectional"))
      (node (ref "R3") (pin "2") (pinfunction "2_2") (pintype "bidirectional"))
    )
    (net (code "33") (name "/RCH1") (class "Default")
      (node (ref "IC3") (pin "4") (pinfunction "Y0_4") (pintype "bidirectional"))
      (node (ref "Q1") (pin "S") (pinfunction "S_S") (pintype "passive"))
    )
    (net (code "34") (name "/RCH2") (class "Default")
      (node (ref "IC3") (pin "7") (pinfunction "Y1_7") (pintype "bidirectional"))
      (node (ref "Q2") (pin "S") (pinfunction "S_S") (pintype "passive"))
    )
    (net (code "35") (name "/RC_3V3") (class "Default")
      (node (ref "C22") (pin "2") (pinfunction "2_2") (pintype "passive"))
      (node (ref "IC5") (pin "5") (pinfunction "VOUT_5") (pintype "output"))
      (node (ref "U$14") (pin "5") (pinfunction "VCC_5") (pintype "bidirectional"))
      (node (ref "U$20") (pin "5") (pinfunction "VCC_5") (pintype "bidirectional"))
      (node (ref "U$23") (pin "5") (pinfunction "VCC_5") (pintype "bidirectional"))
    )
    (net (code "36") (name "/RX") (class "Default")
      (node (ref "IC2") (pin "10") (pinfunction "RX_10") (pintype "bidirectional"))
    )
    (net (code "37") (name "/SCL") (class "Default")
      (node (ref "IC1") (pin "28") (pinfunction "PC5(ADC5/SCL)_28") (pintype "bidirectional"))
      (node (ref "IC2") (pin "5") (pinfunction "SCL_5") (pintype "bidirectional"))
      (node (ref "IC4") (pin "26") (pinfunction "SCL_26") (pintype "bidirectional"))
      (node (ref "R7") (pin "2") (pinfunction "2_2") (pintype "bidirectional"))
      (node (ref "U1") (pin "13") (pinfunction "D0_13") (pintype "bidirectional"))
    )
    (net (code "38") (name "/SCLK") (class "Default")
      (node (ref "IC2") (pin "23") (pinfunction "SCLK_23") (pintype "bidirectional"))
    )
    (net (code "39") (name "/SDA") (class "Default")
      (node (ref "IC1") (pin "27") (pinfunction "PC4(ADC4/SDA)_27") (pintype "bidirectional"))
      (node (ref "IC2") (pin "3") (pinfunction "SDA_3") (pintype "bidirectional"))
      (node (ref "IC4") (pin "27") (pinfunction "SDA_27") (pintype "bidirectional"))
      (node (ref "R9") (pin "2") (pinfunction "2_2") (pintype "bidirectional"))
      (node (ref "U1") (pin "11") (pinfunction "D2_11") (pintype "bidirectional"))
      (node (ref "U1") (pin "12") (pinfunction "D1_12") (pintype "bidirectional"))
    )
    (net (code "40") (name "/SEL") (class "Default")
      (node (ref "IC1") (pin "32") (pinfunction "PD2(INT0)_32") (pintype "bidirectional"))
      (node (ref "IC3") (pin "1") (pinfunction "SEL_1") (pintype "bidirectional"))
      (node (ref "R16") (pin "2") (pinfunction "2_2") (pintype "bidirectional"))
    )
    (net (code "41") (name "/TX") (class "Default")
      (node (ref "IC2") (pin "8") (pinfunction "TX_8") (pintype "bidirectional"))
    )
    (net (code "42") (name "/VCC_RC") (class "Default")
      (node (ref "1") (pin "VCC") (pinfunction "VCC_VCC") (pintype "bidirectional"))
      (node (ref "2") (pin "VCC") (pinfunction "VCC_VCC") (pintype "bidirectional"))
      (node (ref "3") (pin "VCC") (pinfunction "VCC_VCC") (pintype "bidirectional"))
      (node (ref "D5") (pin "2") (pinfunction "A_2") (pintype "passive"))
      (node (ref "JP2") (pin "3") (pinfunction "3_3") (pintype "passive"))
      (node (ref "R15") (pin "2") (pinfunction "2_2") (pintype "bidirectional"))
      (node (ref "R21") (pin "2") (pinfunction "2_2") (pintype "bidirectional"))
      (node (ref "R26") (pin "2") (pinfunction "2_2") (pintype "bidirectional"))
      (node (ref "R30") (pin "2") (pinfunction "2_2") (pintype "bidirectional"))
      (node (ref "R4") (pin "2") (pinfunction "2_2") (pintype "bidirectional"))
      (node (ref "R6") (pin "2") (pinfunction "2_2") (pintype "bidirectional"))
      (node (ref "ST") (pin "VCC") (pinfunction "VCC_VCC") (pintype "bidirectional"))
      (node (ref "TH") (pin "VCC") (pinfunction "VCC_VCC") (pintype "bidirectional"))
    )
    (net (code "43") (name "3V3") (class "Default")
      (node (ref "C12") (pin "2") (pinfunction "2_2") (pintype "passive"))
      (node (ref "C2") (pin "2") (pinfunction "2_2") (pintype "passive"))
      (node (ref "C20") (pin "2") (pinfunction "2_2") (pintype "passive"))
      (node (ref "C24") (pin "2") (pinfunction "2_2") (pintype "passive"))
      (node (ref "C3") (pin "2") (pinfunction "2_2") (pintype "passive"))
      (node (ref "C6") (pin "2") (pinfunction "2_2") (pintype "passive"))
      (node (ref "C7") (pin "2") (pinfunction "2_2") (pintype "passive"))
      (node (ref "D1") (pin "CATHODE") (pinfunction "CATHODE_CATHODE") (pintype "bidirectional"))
      (node (ref "IC1") (pin "18") (pinfunction "AVCC_18") (pintype "bidirectional"))
      (node (ref "IC1") (pin "4") (pinfunction "VCC_4") (pintype "bidirectional"))
      (node (ref "IC1") (pin "6") (pinfunction "VCC_6") (pintype "bidirectional"))
      (node (ref "IC2") (pin "1") (pinfunction "3V3_1") (pintype "bidirectional"))
      (node (ref "IC2") (pin "17") (pinfunction "3V3_17") (pintype "bidirectional"))
      (node (ref "IC3") (pin "16") (pinfunction "VCC_16") (pintype "bidirectional"))
      (node (ref "IC4") (pin "28") (pinfunction "VDD_28") (pintype "bidirectional"))
      (node (ref "ICSP1") (pin "2") (pinfunction "2_2") (pintype "passive"))
      (node (ref "JP2") (pin "1") (pinfunction "1_1") (pintype "passive"))
      (node (ref "R11") (pin "2") (pinfunction "2_2") (pintype "bidirectional"))
      (node (ref "R18") (pin "2") (pinfunction "2_2") (pintype "bidirectional"))
      (node (ref "R2") (pin "2") (pinfunction "2_2") (pintype "bidirectional"))
      (node (ref "R22") (pin "1") (pinfunction "1_1") (pintype "bidirectional"))
      (node (ref "R23") (pin "1") (pinfunction "1_1") (pintype "bidirectional"))
      (node (ref "R41") (pin "2") (pinfunction "2_2") (pintype "bidirectional"))
      (node (ref "R7") (pin "1") (pinfunction "1_1") (pintype "bidirectional"))
      (node (ref "R9") (pin "1") (pinfunction "1_1") (pintype "bidirectional"))
      (node (ref "U1") (pin "22") (pinfunction "VDD_22") (pintype "bidirectional"))
      (node (ref "U1") (pin "25") (pinfunction "VBAT_25") (pintype "bidirectional"))
    )
    (net (code "44") (name "5V") (class "Default")
      (node (ref "IC2") (pin "2") (pinfunction "5V_2") (pintype "bidirectional"))
      (node (ref "SPI-LED") (pin "VCC") (pinfunction "VCC_VCC") (pintype "bidirectional"))
    )
    (net (code "45") (name "AVR_MISO") (class "Default")
      (node (ref "IC1") (pin "16") (pinfunction "PB4(MISO)_16") (pintype "bidirectional"))
      (node (ref "ICSP1") (pin "1") (pinfunction "1_1") (pintype "passive"))
    )
    (net (code "46") (name "AVR_MOSI") (class "Default")
      (node (ref "IC1") (pin "15") (pinfunction "PB3(MOSI/OC2)_15") (pintype "bidirectional"))
      (node (ref "ICSP1") (pin "4") (pinfunction "4_4") (pintype "passive"))
      (node (ref "SPI-LED") (pin "DI") (pinfunction "DI_DI") (pintype "bidirectional"))
    )
    (net (code "47") (name "AVR_RESET") (class "Default")
      (node (ref "IC1") (pin "29") (pinfunction "PC6(/RESET)_29") (pintype "bidirectional"))
      (node (ref "ICSP1") (pin "5") (pinfunction "5_5") (pintype "passive"))
      (node (ref "R2") (pin "1") (pinfunction "1_1") (pintype "bidirectional"))
    )
    (net (code "48") (name "AVR_SCK") (class "Default")
      (node (ref "IC1") (pin "17") (pinfunction "PB5(SCK)_17") (pintype "bidirectional"))
      (node (ref "ICSP1") (pin "3") (pinfunction "3_3") (pintype "passive"))
      (node (ref "SPI-LED") (pin "CI") (pinfunction "CI_CI") (pintype "bidirectional"))
    )
    (net (code "49") (name "GND") (class "Default")
      (node (ref "1") (pin "GND") (pinfunction "GND_GND") (pintype "bidirectional"))
      (node (ref "2") (pin "GND") (pinfunction "GND_GND") (pintype "bidirectional"))
      (node (ref "3") (pin "GND") (pinfunction "GND_GND") (pintype "bidirectional"))
      (node (ref "C1") (pin "1") (pinfunction "1_1") (pintype "passive"))
      (node (ref "C10") (pin "1") (pinfunction "1_1") (pintype "passive"))
      (node (ref "C11") (pin "1") (pinfunction "1_1") (pintype "passive"))
      (node (ref "C12") (pin "1") (pinfunction "1_1") (pintype "passive"))
      (node (ref "C2") (pin "1") (pinfunction "1_1") (pintype "passive"))
      (node (ref "C20") (pin "1") (pinfunction "1_1") (pintype "passive"))
      (node (ref "C22") (pin "1") (pinfunction "1_1") (pintype "passive"))
      (node (ref "C23") (pin "1") (pinfunction "1_1") (pintype "passive"))
      (node (ref "C24") (pin "1") (pinfunction "1_1") (pintype "passive"))
      (node (ref "C3") (pin "1") (pinfunction "1_1") (pintype "passive"))
      (node (ref "C6") (pin "1") (pinfunction "1_1") (pintype "passive"))
      (node (ref "C7") (pin "1") (pinfunction "1_1") (pintype "passive"))
      (node (ref "C8") (pin "1") (pinfunction "1_1") (pintype "passive"))
      (node (ref "C9") (pin "1") (pinfunction "1_1") (pintype "passive"))
      (node (ref "CN1") (pin "3") (pinfunction "3_3") (pintype "bidirectional"))
      (node (ref "IC1") (pin "21") (pinfunction "GND_21") (pintype "bidirectional"))
      (node (ref "IC1") (pin "3") (pinfunction "GND_3") (pintype "bidirectional"))
      (node (ref "IC1") (pin "5") (pinfunction "AGND_5") (pintype "bidirectional"))
      (node (ref "IC2") (pin "14") (pinfunction "GND_14") (pintype "bidirectional"))
      (node (ref "IC2") (pin "20") (pinfunction "GND_20") (pintype "bidirectional"))
      (node (ref "IC2") (pin "25") (pinfunction "GND_25") (pintype "bidirectional"))
      (node (ref "IC2") (pin "30") (pinfunction "GND_30") (pintype "bidirectional"))
      (node (ref "IC2") (pin "34") (pinfunction "GND_34") (pintype "bidirectional"))
      (node (ref "IC2") (pin "39") (pinfunction "GND_39") (pintype "bidirectional"))
      (node (ref "IC2") (pin "9") (pinfunction "GND_9") (pintype "bidirectional"))
      (node (ref "IC3") (pin "15") (pinfunction "EN_15") (pintype "bidirectional"))
      (node (ref "IC3") (pin "8") (pinfunction "GND_8") (pintype "bidirectional"))
      (node (ref "IC4") (pin "1") (pinfunction "A0_1") (pintype "bidirectional"))
      (node (ref "IC4") (pin "14") (pinfunction "VSS_14") (pintype "bidirectional"))
      (node (ref "IC4") (pin "2") (pinfunction "A1_2") (pintype "bidirectional"))
      (node (ref "IC4") (pin "24") (pinfunction "A5_24") (pintype "bidirectional"))
      (node (ref "IC4") (pin "3") (pinfunction "A2_3") (pintype "bidirectional"))
      (node (ref "IC4") (pin "4") (pinfunction "A3_4") (pintype "bidirectional"))
      (node (ref "IC4") (pin "5") (pinfunction "A4_5") (pintype "bidirectional"))
      (node (ref "IC5") (pin "2") (pinfunction "GND_2") (pintype "power_in"))
      (node (ref "ICSP1") (pin "6") (pinfunction "6_6") (pintype "passive"))
      (node (ref "M1") (pin "S") (pinfunction "S_S") (pintype "passive"))
      (node (ref "M2") (pin "S") (pinfunction "S_S") (pintype "passive"))
      (node (ref "M3") (pin "S") (pinfunction "S_S") (pintype "passive"))
      (node (ref "M4") (pin "S") (pinfunction "S_S") (pintype "passive"))
      (node (ref "M5") (pin "S") (pinfunction "S_S") (pintype "passive"))
      (node (ref "M6") (pin "S") (pinfunction "S_S") (pintype "passive"))
      (node (ref "R1") (pin "1") (pinfunction "1_1") (pintype "bidirectional"))
      (node (ref "R10") (pin "1") (pinfunction "1_1") (pintype "bidirectional"))
      (node (ref "R16") (pin "1") (pinfunction "1_1") (pintype "bidirectional"))
      (node (ref "R24") (pin "1") (pinfunction "1_1") (pintype "bidirectional"))
      (node (ref "R27") (pin "1") (pinfunction "1_1") (pintype "bidirectional"))
      (node (ref "R3") (pin "1") (pinfunction "1_1") (pintype "bidirectional"))
      (node (ref "R31") (pin "1") (pinfunction "1_1") (pintype "bidirectional"))
      (node (ref "R35") (pin "2") (pinfunction "2_2") (pintype "bidirectional"))
      (node (ref "R36") (pin "2") (pinfunction "2_2") (pintype "bidirectional"))
      (node (ref "R38") (pin "2") (pinfunction "2_2") (pintype "bidirectional"))
      (node (ref "R40") (pin "2") (pinfunction "2_2") (pintype "bidirectional"))
      (node (ref "R5") (pin "1") (pinfunction "1_1") (pintype "bidirectional"))
      (node (ref "SPI-LED") (pin "GND") (pinfunction "GND_GND") (pintype "bidirectional"))
      (node (ref "ST") (pin "GND") (pinfunction "GND_GND") (pintype "bidirectional"))
      (node (ref "SW1") (pin "1") (pinfunction "1_1") (pintype "passive"))
      (node (ref "SW1") (pin "2") (pinfunction "2_2") (pintype "passive"))
      (node (ref "TH") (pin "GND") (pinfunction "GND_GND") (pintype "bidirectional"))
      (node (ref "U$14") (pin "3") (pinfunction "GND_3") (pintype "bidirectional"))
      (node (ref "U$20") (pin "3") (pinfunction "GND_3") (pintype "bidirectional"))
      (node (ref "U$23") (pin "3") (pinfunction "GND_3") (pintype "bidirectional"))
      (node (ref "U1") (pin "10") (pinfunction "D3_10") (pintype "bidirectional"))
      (node (ref "U1") (pin "14") (pinfunction "E/RD#_14") (pintype "bidirectional"))
      (node (ref "U1") (pin "15") (pinfunction "R/W#_15") (pintype "bidirectional"))
      (node (ref "U1") (pin "16") (pinfunction "D/C#_16") (pintype "bidirectional"))
      (node (ref "U1") (pin "18") (pinfunction "CS#_18") (pintype "bidirectional"))
      (node (ref "U1") (pin "19") (pinfunction "BS2_19") (pintype "bidirectional"))
      (node (ref "U1") (pin "2") (pinfunction "VLSS_2") (pintype "bidirectional"))
      (node (ref "U1") (pin "21") (pinfunction "BS0_21") (pintype "bidirectional"))
      (node (ref "U1") (pin "23") (pinfunction "VSS_23") (pintype "bidirectional"))
      (node (ref "U1") (pin "6") (pinfunction "D7_6") (pintype "bidirectional"))
      (node (ref "U1") (pin "7") (pinfunction "D6_7") (pintype "bidirectional"))
      (node (ref "U1") (pin "8") (pinfunction "D5_8") (pintype "bidirectional"))
      (node (ref "U1") (pin "9") (pinfunction "D4_9") (pintype "bidirectional"))
      (node (ref "X2") (pin "2") (pinfunction "2_2") (pintype "passive"))
    )
    (net (code "50") (name "Net-(1-PadI{slash}O)") (class "Default")
      (node (ref "1") (pin "I/O") (pinfunction "I/O_I/O") (pintype "bidirectional"))
      (node (ref "R28") (pin "2") (pinfunction "2_2") (pintype "bidirectional"))
    )
    (net (code "51") (name "Net-(2-PadI{slash}O)") (class "Default")
      (node (ref "2") (pin "I/O") (pinfunction "I/O_I/O") (pintype "bidirectional"))
      (node (ref "R37") (pin "2") (pinfunction "2_2") (pintype "bidirectional"))
    )
    (net (code "52") (name "Net-(3-PadI{slash}O)") (class "Default")
      (node (ref "3") (pin "I/O") (pinfunction "I/O_I/O") (pintype "bidirectional"))
      (node (ref "R39") (pin "2") (pinfunction "2_2") (pintype "bidirectional"))
    )
    (net (code "53") (name "Net-(C11-Pad2)") (class "Default")
      (node (ref "C11") (pin "2") (pinfunction "2_2") (pintype "passive"))
      (node (ref "D1") (pin "ANODE") (pinfunction "ANODE_ANODE") (pintype "bidirectional"))
      (node (ref "R23") (pin "2") (pinfunction "2_2") (pintype "bidirectional"))
      (node (ref "R8") (pin "1") (pinfunction "1_1") (pintype "bidirectional"))
    )
    (net (code "54") (name "Net-(CN1-Pad1)") (class "Default")
      (node (ref "CN1") (pin "1") (pinfunction "1_1") (pintype "bidirectional"))
      (node (ref "R12") (pin "1") (pinfunction "1_1") (pintype "bidirectional"))
    )
    (net (code "55") (name "Net-(CN1-Pad2)") (class "Default")
      (node (ref "CN1") (pin "2") (pinfunction "2_2") (pintype "bidirectional"))
      (node (ref "R13") (pin "1") (pinfunction "1_1") (pintype "bidirectional"))
    )
    (net (code "56") (name "Net-(D2-A)") (class "Default")
      (node (ref "D2") (pin "2") (pinfunction "A_2") (pintype "passive"))
      (node (ref "M4") (pin "D") (pinfunction "D_D") (pintype "passive"))
      (node (ref "R21") (pin "1") (pinfunction "1_1") (pintype "bidirectional"))
    )
    (net (code "57") (name "Net-(D2-C)") (class "Default")
      (node (ref "D2") (pin "1") (pinfunction "C_1") (pintype "passive"))
      (node (ref "R24") (pin "2") (pinfunction "2_2") (pintype "bidirectional"))
      (node (ref "U$20") (pin "2") (pinfunction "A_2") (pintype "bidirectional"))
    )
    (net (code "58") (name "Net-(D3-A)") (class "Default")
      (node (ref "D3") (pin "2") (pinfunction "A_2") (pintype "passive"))
      (node (ref "M2") (pin "D") (pinfunction "D_D") (pintype "passive"))
      (node (ref "R6") (pin "1") (pinfunction "1_1") (pintype "bidirectional"))
    )
    (net (code "59") (name "Net-(D3-C)") (class "Default")
      (node (ref "D3") (pin "1") (pinfunction "C_1") (pintype "passive"))
      (node (ref "R27") (pin "2") (pinfunction "2_2") (pintype "bidirectional"))
      (node (ref "U$14") (pin "2") (pinfunction "A_2") (pintype "bidirectional"))
    )
    (net (code "60") (name "Net-(D4-A)") (class "Default")
      (node (ref "D4") (pin "2") (pinfunction "A_2") (pintype "passive"))
      (node (ref "M6") (pin "D") (pinfunction "D_D") (pintype "passive"))
      (node (ref "R30") (pin "1") (pinfunction "1_1") (pintype "bidirectional"))
    )
    (net (code "61") (name "Net-(D4-C)") (class "Default")
      (node (ref "D4") (pin "1") (pinfunction "C_1") (pintype "passive"))
      (node (ref "R31") (pin "2") (pinfunction "2_2") (pintype "bidirectional"))
      (node (ref "U$23") (pin "2") (pinfunction "A_2") (pintype "bidirectional"))
    )
    (net (code "62") (name "Net-(D5-C)") (class "Default")
      (node (ref "C10") (pin "2") (pinfunction "2_2") (pintype "passive"))
      (node (ref "D5") (pin "1") (pinfunction "C_1") (pintype "passive"))
      (node (ref "IC5") (pin "1") (pinfunction "VIN_1") (pintype "input"))
      (node (ref "IC5") (pin "3") (pinfunction "ON/OFF_3") (pintype "input"))
    )
    (net (code "63") (name "Net-(IC1-ADC6)") (class "Default")
      (node (ref "IC1") (pin "19") (pinfunction "ADC6_19") (pintype "bidirectional"))
      (node (ref "R41") (pin "1") (pinfunction "1_1") (pintype "bidirectional"))
      (node (ref "SW1") (pin "3") (pinfunction "3_3") (pintype "passive"))
      (node (ref "SW1") (pin "4") (pinfunction "4_4") (pintype "passive"))
    )
    (net (code "64") (name "Net-(IC1-AREF)") (class "Default")
      (node (ref "C1") (pin "2") (pinfunction "2_2") (pintype "passive"))
      (node (ref "IC1") (pin "20") (pinfunction "AREF_20") (pintype "bidirectional"))
    )
    (net (code "65") (name "Net-(IC1-PB6(XTAL1{slash}TOSC1))") (class "Default")
      (node (ref "IC1") (pin "7") (pinfunction "PB6(XTAL1/TOSC1)_7") (pintype "bidirectional"))
      (node (ref "X2") (pin "1") (pinfunction "1_1") (pintype "passive"))
    )
    (net (code "66") (name "Net-(IC1-PB7(XTAL2{slash}TOSC2))") (class "Default")
      (node (ref "IC1") (pin "8") (pinfunction "PB7(XTAL2/TOSC2)_8") (pintype "bidirectional"))
      (node (ref "X2") (pin "3") (pinfunction "3_3") (pintype "passive"))
    )
    (net (code "67") (name "Net-(IC4-EXTCLK)") (class "Default")
      (node (ref "IC4") (pin "25") (pinfunction "EXTCLK_25") (pintype "bidirectional"))
      (node (ref "R1") (pin "2") (pinfunction "2_2") (pintype "bidirectional"))
    )
    (net (code "68") (name "Net-(IC4-LED0)") (class "Default")
      (node (ref "IC4") (pin "6") (pinfunction "LED0_6") (pintype "bidirectional"))
      (node (ref "R33") (pin "2") (pinfunction "2_2") (pintype "bidirectional"))
    )
    (net (code "69") (name "Net-(IC4-LED1)") (class "Default")
      (node (ref "IC4") (pin "7") (pinfunction "LED1_7") (pintype "bidirectional"))
      (node (ref "R34") (pin "2") (pinfunction "2_2") (pintype "bidirectional"))
    )
    (net (code "70") (name "Net-(IC5-BYPASS)") (class "Default")
      (node (ref "C23") (pin "2") (pinfunction "2_2") (pintype "passive"))
      (node (ref "IC5") (pin "4") (pinfunction "BYPASS_4") (pintype "bidirectional"))
    )
    (net (code "71") (name "Net-(JETSON-PadCATHODE)") (class "Default")
      (node (ref "JETSON") (pin "CATHODE") (pinfunction "CATHODE_CATHODE") (pintype "passive"))
      (node (ref "R10") (pin "2") (pinfunction "2_2") (pintype "bidirectional"))
    )
    (net (code "72") (name "Net-(JETSON1-PadCATHODE)") (class "Default")
      (node (ref "JETSON1") (pin "CATHODE") (pinfunction "CATHODE_CATHODE") (pintype "passive"))
      (node (ref "R5") (pin "2") (pinfunction "2_2") (pintype "bidirectional"))
    )
    (net (code "73") (name "Net-(JP2-Pad2)") (class "Default")
      (node (ref "JP2") (pin "2") (pinfunction "2_2") (pintype "passive"))
      (node (ref "R14") (pin "2") (pinfunction "2_2") (pintype "bidirectional"))
      (node (ref "R19") (pin "2") (pinfunction "2_2") (pintype "bidirectional"))
    )
    (net (code "74") (name "Net-(M1-PadD)") (class "Default")
      (node (ref "M1") (pin "D") (pinfunction "D_D") (pintype "passive"))
      (node (ref "M2") (pin "G") (pinfunction "G_G") (pintype "passive"))
      (node (ref "R4") (pin "1") (pinfunction "1_1") (pintype "bidirectional"))
    )
    (net (code "75") (name "Net-(M1-PadG)") (class "Default")
      (node (ref "M1") (pin "G") (pinfunction "G_G") (pintype "passive"))
      (node (ref "R28") (pin "1") (pinfunction "1_1") (pintype "bidirectional"))
      (node (ref "R36") (pin "1") (pinfunction "1_1") (pintype "bidirectional"))
    )
    (net (code "76") (name "Net-(M3-PadD)") (class "Default")
      (node (ref "M3") (pin "D") (pinfunction "D_D") (pintype "passive"))
      (node (ref "M4") (pin "G") (pinfunction "G_G") (pintype "passive"))
      (node (ref "R15") (pin "1") (pinfunction "1_1") (pintype "bidirectional"))
    )
    (net (code "77") (name "Net-(M3-PadG)") (class "Default")
      (node (ref "M3") (pin "G") (pinfunction "G_G") (pintype "passive"))
      (node (ref "R37") (pin "1") (pinfunction "1_1") (pintype "bidirectional"))
      (node (ref "R38") (pin "1") (pinfunction "1_1") (pintype "bidirectional"))
    )
    (net (code "78") (name "Net-(M5-PadD)") (class "Default")
      (node (ref "M5") (pin "D") (pinfunction "D_D") (pintype "passive"))
      (node (ref "M6") (pin "G") (pinfunction "G_G") (pintype "passive"))
      (node (ref "R26") (pin "1") (pinfunction "1_1") (pintype "bidirectional"))
    )
    (net (code "79") (name "Net-(M5-PadG)") (class "Default")
      (node (ref "M5") (pin "G") (pinfunction "G_G") (pintype "passive"))
      (node (ref "R39") (pin "1") (pinfunction "1_1") (pintype "bidirectional"))
      (node (ref "R40") (pin "1") (pinfunction "1_1") (pintype "bidirectional"))
    )
    (net (code "80") (name "Net-(Q1-PadD)") (class "Default")
      (node (ref "Q1") (pin "D") (pinfunction "D_D") (pintype "passive"))
      (node (ref "R17") (pin "2") (pinfunction "2_2") (pintype "bidirectional"))
      (node (ref "R19") (pin "1") (pinfunction "1_1") (pintype "bidirectional"))
    )
    (net (code "81") (name "Net-(Q1-PadG)") (class "Default")
      (node (ref "Q1") (pin "G") (pinfunction "G_G") (pintype "passive"))
      (node (ref "R18") (pin "1") (pinfunction "1_1") (pintype "bidirectional"))
    )
    (net (code "82") (name "Net-(Q2-PadD)") (class "Default")
      (node (ref "Q2") (pin "D") (pinfunction "D_D") (pintype "passive"))
      (node (ref "R14") (pin "1") (pinfunction "1_1") (pintype "bidirectional"))
      (node (ref "R20") (pin "2") (pinfunction "2_2") (pintype "bidirectional"))
    )
    (net (code "83") (name "Net-(Q2-PadG)") (class "Default")
      (node (ref "Q2") (pin "G") (pinfunction "G_G") (pintype "passive"))
      (node (ref "R11") (pin "1") (pinfunction "1_1") (pintype "bidirectional"))
    )
    (net (code "84") (name "Net-(R17-Pad1)") (class "Default")
      (node (ref "R17") (pin "1") (pinfunction "1_1") (pintype "bidirectional"))
      (node (ref "ST") (pin "I/O") (pinfunction "I/O_I/O") (pintype "bidirectional"))
    )
    (net (code "85") (name "Net-(R20-Pad1)") (class "Default")
      (node (ref "R20") (pin "1") (pinfunction "1_1") (pintype "bidirectional"))
      (node (ref "TH") (pin "I/O") (pinfunction "I/O_I/O") (pintype "bidirectional"))
    )
    (net (code "86") (name "Net-(U$14-Y)") (class "Default")
      (node (ref "R29") (pin "1") (pinfunction "1_1") (pintype "bidirectional"))
      (node (ref "U$14") (pin "4") (pinfunction "Y_4") (pintype "bidirectional"))
    )
    (net (code "87") (name "Net-(U$20-Y)") (class "Default")
      (node (ref "R25") (pin "1") (pinfunction "1_1") (pintype "bidirectional"))
      (node (ref "U$20") (pin "4") (pinfunction "Y_4") (pintype "bidirectional"))
    )
    (net (code "88") (name "Net-(U$23-Y)") (class "Default")
      (node (ref "R32") (pin "1") (pinfunction "1_1") (pintype "bidirectional"))
      (node (ref "U$23") (pin "4") (pinfunction "Y_4") (pintype "bidirectional"))
    )
    (net (code "89") (name "Net-(U1-BS1)") (class "Default")
      (node (ref "R22") (pin "2") (pinfunction "2_2") (pintype "bidirectional"))
      (node (ref "U1") (pin "20") (pinfunction "BS1_20") (pintype "bidirectional"))
    )
    (net (code "90") (name "Net-(U1-C1N)") (class "Default")
      (node (ref "C4") (pin "1") (pinfunction "1_1") (pintype "passive"))
      (node (ref "U1") (pin "26") (pinfunction "C1N_26") (pintype "bidirectional"))
    )
    (net (code "91") (name "Net-(U1-C1P)") (class "Default")
      (node (ref "C4") (pin "2") (pinfunction "2_2") (pintype "passive"))
      (node (ref "U1") (pin "27") (pinfunction "C1P_27") (pintype "bidirectional"))
    )
    (net (code "92") (name "Net-(U1-C2N)") (class "Default")
      (node (ref "C5") (pin "1") (pinfunction "1_1") (pintype "passive"))
      (node (ref "U1") (pin "28") (pinfunction "C2N_28") (pintype "bidirectional"))
    )
    (net (code "93") (name "Net-(U1-C2P)") (class "Default")
      (node (ref "C5") (pin "2") (pinfunction "2_2") (pintype "passive"))
      (node (ref "U1") (pin "29") (pinfunction "C2P_29") (pintype "bidirectional"))
    )
    (net (code "94") (name "Net-(U1-IREF)") (class "Default")
      (node (ref "R35") (pin "1") (pinfunction "1_1") (pintype "bidirectional"))
      (node (ref "U1") (pin "5") (pinfunction "IREF_5") (pintype "bidirectional"))
    )
    (net (code "95") (name "Net-(U1-RES#)") (class "Default")
      (node (ref "R8") (pin "2") (pinfunction "2_2") (pintype "bidirectional"))
      (node (ref "U1") (pin "17") (pinfunction "RES#_17") (pintype "bidirectional"))
    )
    (net (code "96") (name "Net-(U1-VCC)") (class "Default")
      (node (ref "C8") (pin "2") (pinfunction "2_2") (pintype "passive"))
      (node (ref "U1") (pin "3") (pinfunction "VCC_3") (pintype "bidirectional"))
    )
    (net (code "97") (name "Net-(U1-VCOMH)") (class "Default")
      (node (ref "C9") (pin "2") (pinfunction "2_2") (pintype "passive"))
      (node (ref "U1") (pin "4") (pinfunction "VCOMH_4") (pintype "bidirectional"))
    )
    (net (code "98") (name "unconnected-(IC1-PB0(ICP)-Pad12)") (class "Default")
      (node (ref "IC1") (pin "12") (pinfunction "PB0(ICP)_12") (pintype "bidirectional"))
    )
    (net (code "99") (name "unconnected-(IC1-PB1(OC1A)-Pad13)") (class "Default")
      (node (ref "IC1") (pin "13") (pinfunction "PB1(OC1A)_13") (pintype "bidirectional"))
    )
    (net (code "100") (name "unconnected-(IC1-PB2(SS{slash}OC1B)-Pad14)") (class "Default")
      (node (ref "IC1") (pin "14") (pinfunction "PB2(SS/OC1B)_14") (pintype "bidirectional"))
    )
    (net (code "101") (name "unconnected-(IC1-PC2(ADC2)-Pad25)") (class "Default")
      (node (ref "IC1") (pin "25") (pinfunction "PC2(ADC2)_25") (pintype "bidirectional"))
    )
    (net (code "102") (name "unconnected-(IC1-PD5(T1)-Pad9)") (class "Default")
      (node (ref "IC1") (pin "9") (pinfunction "PD5(T1)_9") (pintype "bidirectional"))
    )
    (net (code "103") (name "unconnected-(IC1-PD6(AIN0)-Pad10)") (class "Default")
      (node (ref "IC1") (pin "10") (pinfunction "PD6(AIN0)_10") (pintype "bidirectional"))
    )
    (net (code "104") (name "unconnected-(IC1-PD7(AIN1)-Pad11)") (class "Default")
      (node (ref "IC1") (pin "11") (pinfunction "PD7(AIN1)_11") (pintype "bidirectional"))
    )
    (net (code "105") (name "unconnected-(IC2-CE1-Pad26)") (class "Default")
      (node (ref "IC2") (pin "26") (pinfunction "CE1_26") (pintype "bidirectional"))
    )
    (net (code "106") (name "unconnected-(IC2-ID_SC-Pad28)") (class "Default")
      (node (ref "IC2") (pin "28") (pinfunction "ID_SC_28") (pintype "bidirectional"))
    )
    (net (code "107") (name "unconnected-(IC2-ID_SD-Pad27)") (class "Default")
      (node (ref "IC2") (pin "27") (pinfunction "ID_SD_27") (pintype "bidirectional"))
    )
    (net (code "108") (name "unconnected-(IC3-A2-Pad11)") (class "Default")
      (node (ref "IC3") (pin "11") (pinfunction "A2_11") (pintype "bidirectional"))
    )
    (net (code "109") (name "unconnected-(IC3-A3-Pad14)") (class "Default")
      (node (ref "IC3") (pin "14") (pinfunction "A3_14") (pintype "bidirectional"))
    )
    (net (code "110") (name "unconnected-(IC3-B2-Pad10)") (class "Default")
      (node (ref "IC3") (pin "10") (pinfunction "B2_10") (pintype "bidirectional"))
    )
    (net (code "111") (name "unconnected-(IC3-B3-Pad13)") (class "Default")
      (node (ref "IC3") (pin "13") (pinfunction "B3_13") (pintype "bidirectional"))
    )
    (net (code "112") (name "unconnected-(IC3-Y2-Pad9)") (class "Default")
      (node (ref "IC3") (pin "9") (pinfunction "Y2_9") (pintype "bidirectional"))
    )
    (net (code "113") (name "unconnected-(IC3-Y3-Pad12)") (class "Default")
      (node (ref "IC3") (pin "12") (pinfunction "Y3_12") (pintype "bidirectional"))
    )
    (net (code "114") (name "unconnected-(IC4-LED2-Pad8)") (class "Default")
      (node (ref "IC4") (pin "8") (pinfunction "LED2_8") (pintype "bidirectional"))
    )
    (net (code "115") (name "unconnected-(IC4-LED3-Pad9)") (class "Default")
      (node (ref "IC4") (pin "9") (pinfunction "LED3_9") (pintype "bidirectional"))
    )
    (net (code "116") (name "unconnected-(IC4-LED4-Pad10)") (class "Default")
      (node (ref "IC4") (pin "10") (pinfunction "LED4_10") (pintype "bidirectional"))
    )
    (net (code "117") (name "unconnected-(IC4-LED5-Pad11)") (class "Default")
      (node (ref "IC4") (pin "11") (pinfunction "LED5_11") (pintype "bidirectional"))
    )
    (net (code "118") (name "unconnected-(IC4-LED6-Pad12)") (class "Default")
      (node (ref "IC4") (pin "12") (pinfunction "LED6_12") (pintype "bidirectional"))
    )
    (net (code "119") (name "unconnected-(IC4-LED7-Pad13)") (class "Default")
      (node (ref "IC4") (pin "13") (pinfunction "LED7_13") (pintype "bidirectional"))
    )
    (net (code "120") (name "unconnected-(IC4-LED8-Pad15)") (class "Default")
      (node (ref "IC4") (pin "15") (pinfunction "LED8_15") (pintype "bidirectional"))
    )
    (net (code "121") (name "unconnected-(IC4-LED9-Pad16)") (class "Default")
      (node (ref "IC4") (pin "16") (pinfunction "LED9_16") (pintype "bidirectional"))
    )
    (net (code "122") (name "unconnected-(IC4-LED10-Pad17)") (class "Default")
      (node (ref "IC4") (pin "17") (pinfunction "LED10_17") (pintype "bidirectional"))
    )
    (net (code "123") (name "unconnected-(IC4-LED11-Pad18)") (class "Default")
      (node (ref "IC4") (pin "18") (pinfunction "LED11_18") (pintype "bidirectional"))
    )
    (net (code "124") (name "unconnected-(IC4-LED12-Pad19)") (class "Default")
      (node (ref "IC4") (pin "19") (pinfunction "LED12_19") (pintype "bidirectional"))
    )
    (net (code "125") (name "unconnected-(IC4-LED13-Pad20)") (class "Default")
      (node (ref "IC4") (pin "20") (pinfunction "LED13_20") (pintype "bidirectional"))
    )
    (net (code "126") (name "unconnected-(IC4-LED14-Pad21)") (class "Default")
      (node (ref "IC4") (pin "21") (pinfunction "LED14_21") (pintype "bidirectional"))
    )
    (net (code "127") (name "unconnected-(IC4-LED15-Pad22)") (class "Default")
      (node (ref "IC4") (pin "22") (pinfunction "LED15_22") (pintype "bidirectional"))
    )
    (net (code "128") (name "unconnected-(U1-NC-Pad1)") (class "Default")
      (node (ref "U1") (pin "1") (pinfunction "NC_1") (pintype "bidirectional"))
    )
    (net (code "129") (name "unconnected-(U1-NC-Pad24)") (class "Default")
      (node (ref "U1") (pin "24") (pinfunction "NC_24") (pintype "bidirectional"))
    )
    (net (code "130") (name "unconnected-(U1-NC-Pad30)") (class "Default")
      (node (ref "U1") (pin "30") (pinfunction "NC_30") (pintype "bidirectional"))
    )
  )
)
